# SDA381V3.net
KiCad netlist of a schematic drawn in EAGLE
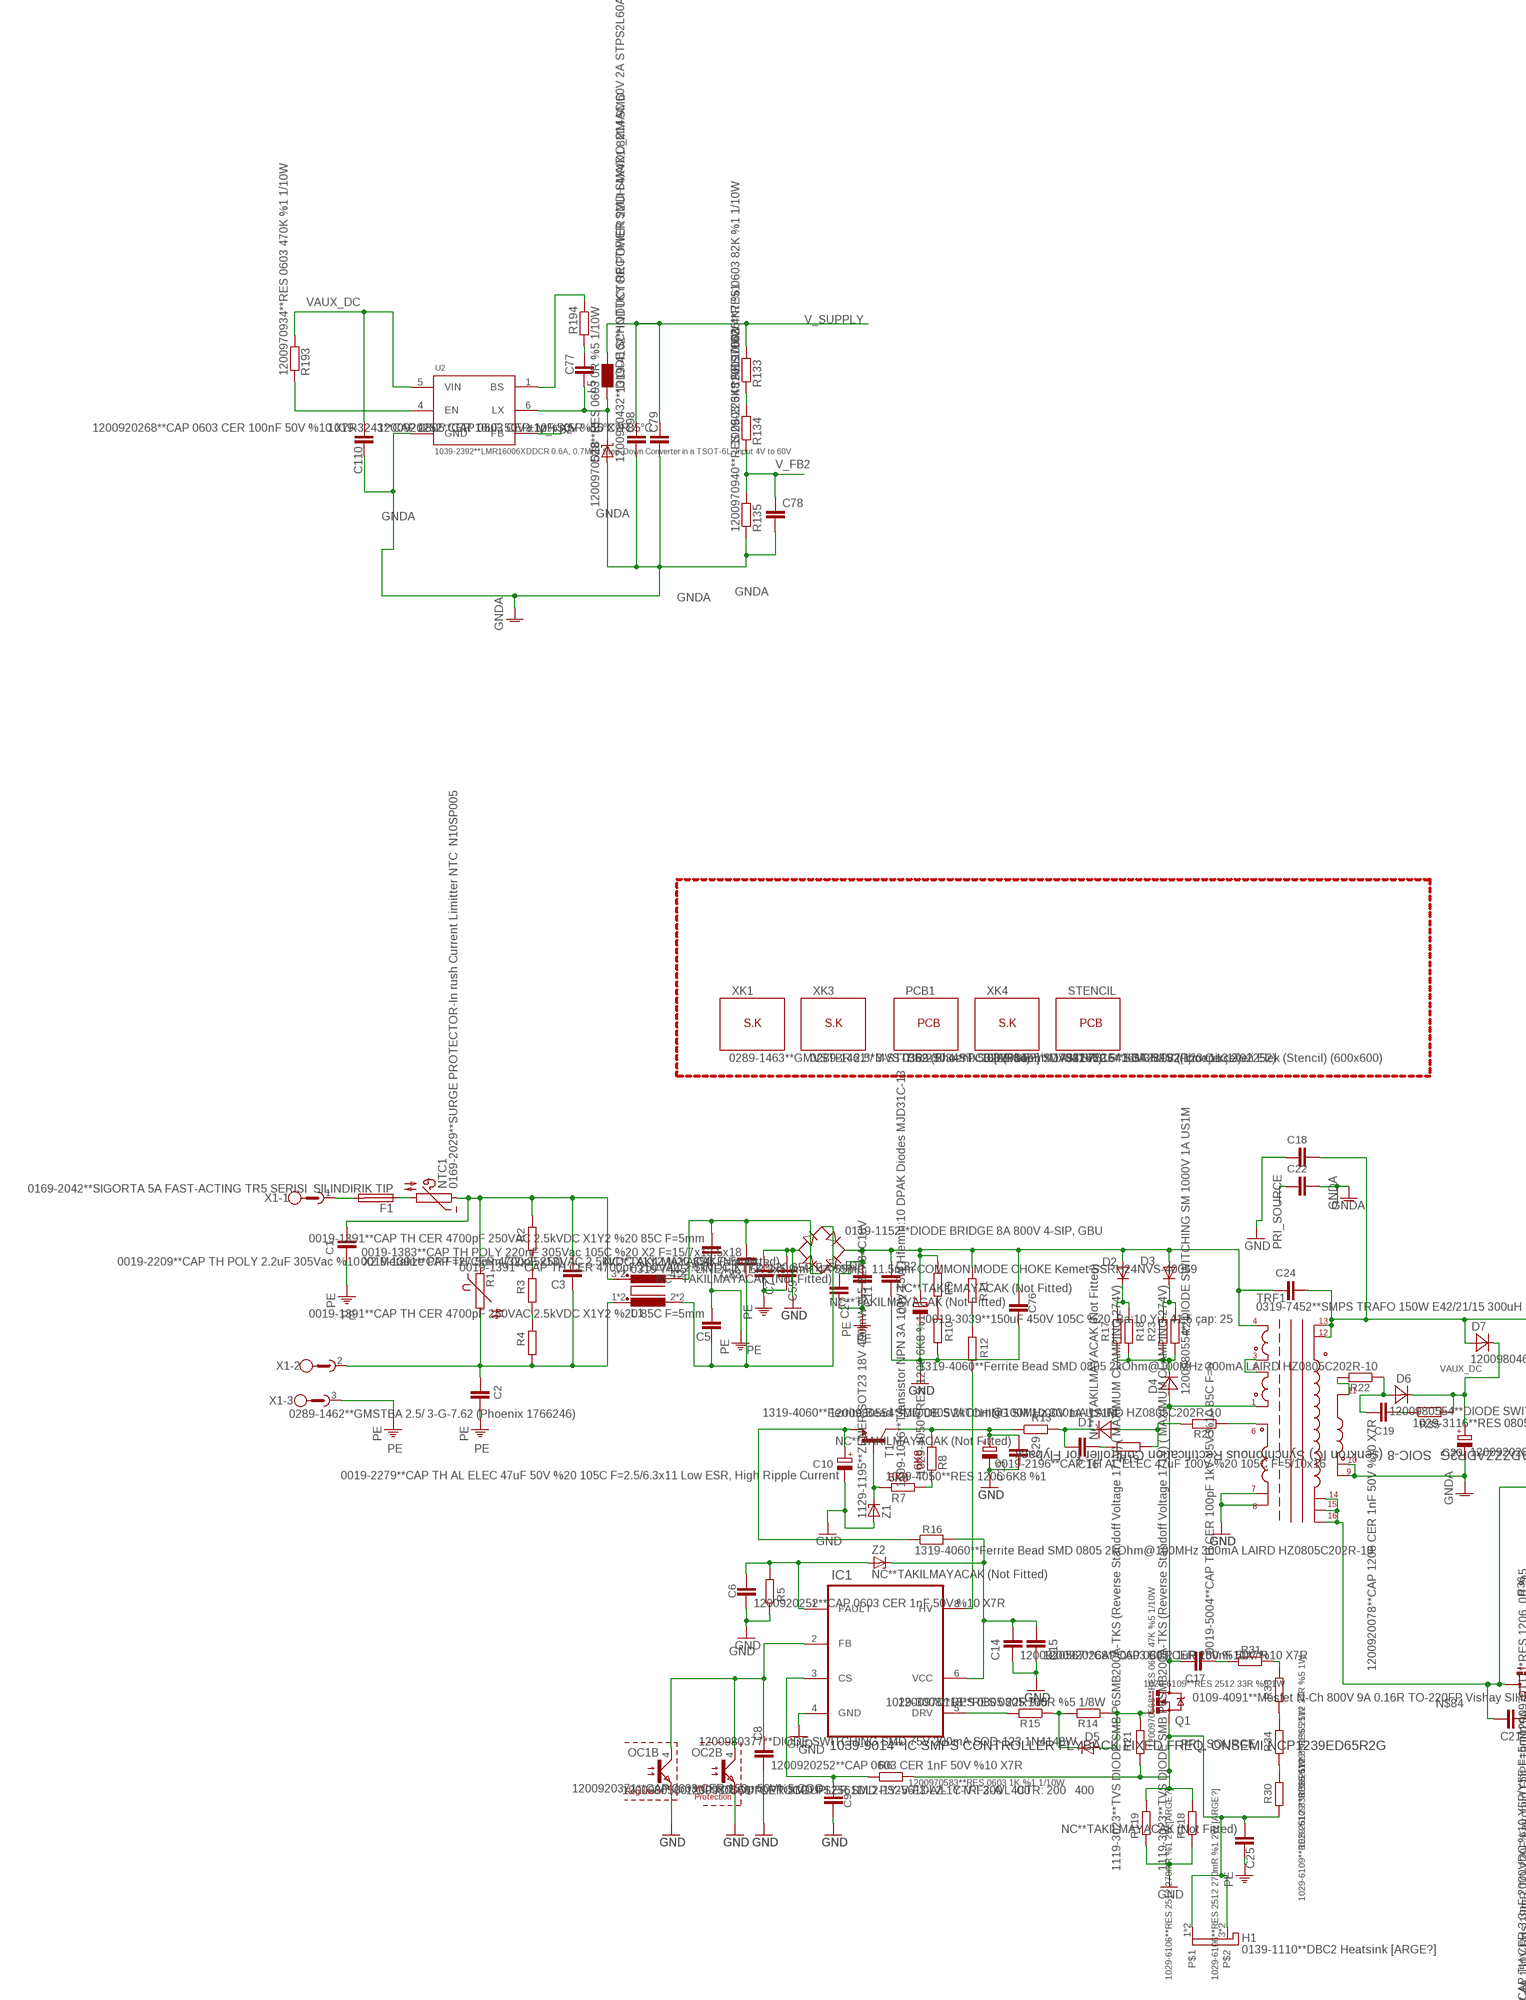
[diagram p0: schematic, sheet 1, part 1 of 3]
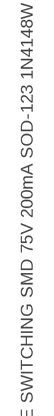
[diagram p1: schematic, sheet 1, part 2 of 3]
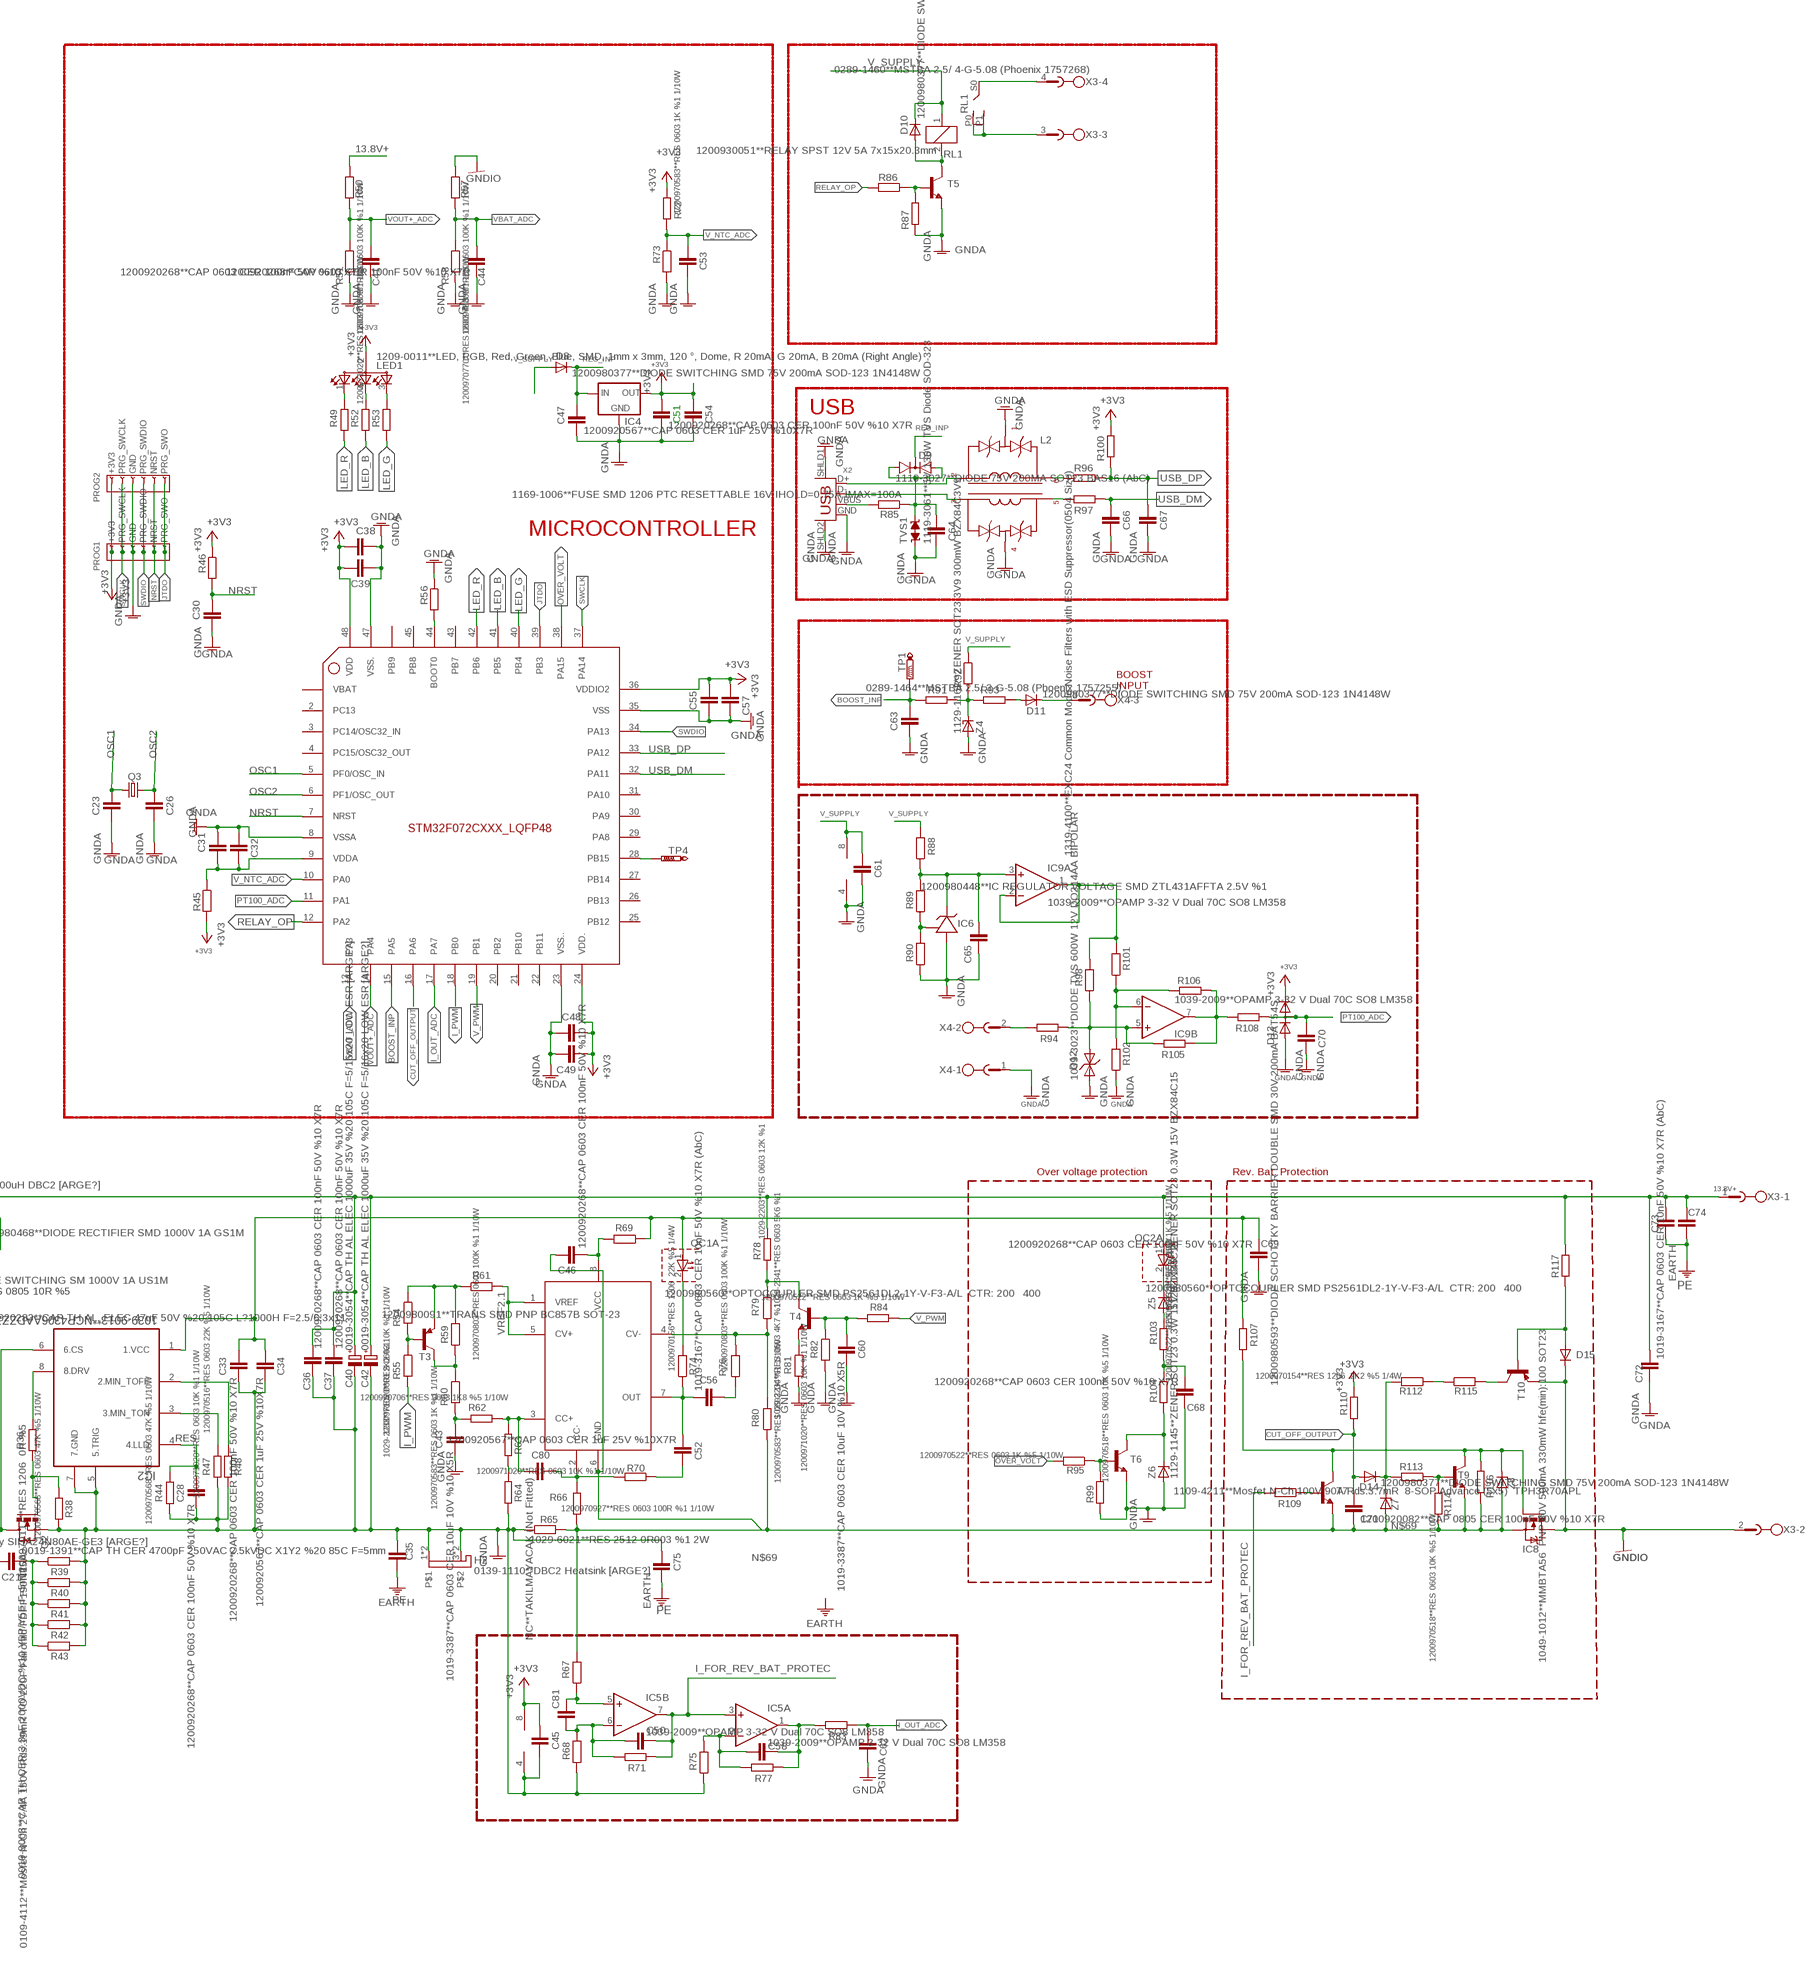
[diagram p2: schematic, sheet 1, part 3 of 3]

(export (version "E")
  (design (tool "Eeschema 10.0.6"))
  (components
    (comp (ref "B1")
      (value "0119-1152**DIODE BRIDGE 8A 800V 4-SIP, GBU")
      (footprint "eagle-import:DıODE_BRIDGE_8A_DIK")
      (libsource (lib "eagle-import") (part "DıODE_BRIDGE_8A_DIK"))
    )
    (comp (ref "C1")
      (value "NC**TAKILMAYACAK (Not Fitted)")
      (footprint "eagle-import:C50-035X75")
      (libsource (lib "eagle-import") (part "C50-035X75"))
    )
    (comp (ref "C2")
      (value "NC**TAKILMAYACAK (Not Fitted)")
      (footprint "eagle-import:C50-035X75")
      (libsource (lib "eagle-import") (part "C50-035X75"))
    )
    (comp (ref "C3")
      (value "0019-2209**CAP TH POLY 2.2uF 305Vac %10 X2 Metalize PP F=27.5mm (32x25x13)")
      (footprint "eagle-import:C275-113X316_&_C150-072X183_&_C225-113X268")
      (libsource (lib "eagle-import") (part "C275-113X316_&_C150-072X183_&_C225-113X268"))
    )
    (comp (ref "C4")
      (value "0019-1391**CAP TH CER 4700pF 250VAC 2.5kVDC X1Y2 %20 85C F=5mm")
      (footprint "eagle-import:C50-035X75")
      (libsource (lib "eagle-import") (part "C50-035X75"))
    )
    (comp (ref "C5")
      (value "0019-1391**CAP TH CER 4700pF 250VAC 2.5kVDC X1Y2 %20 85C F=5mm")
      (footprint "eagle-import:C50-035X75")
      (libsource (lib "eagle-import") (part "C50-035X75"))
    )
    (comp (ref "C6")
      (value "1200920252**CAP 0603 CER 1nF 50V %10 X7R")
      (footprint "eagle-import:C0603_ENKO")
      (libsource (lib "eagle-import") (part "C-EUC0603E"))
    )
    (comp (ref "C7")
      (value "0019-1391**CAP TH CER 4700pF 250VAC 2.5kVDC X1Y2 %20 85C F=5mm")
      (footprint "eagle-import:C50-035X75")
      (libsource (lib "eagle-import") (part "C50-035X75"))
    )
    (comp (ref "C8")
      (value "1200920252**CAP 0603 CER 1nF 50V %10 X7R")
      (footprint "eagle-import:C0603_ENKO")
      (libsource (lib "eagle-import") (part "C-EUC0603E"))
    )
    (comp (ref "C9")
      (value "1200920371**CAP 0603 CER 150p 50V%5 COG")
      (footprint "eagle-import:C0603_ENKO")
      (libsource (lib "eagle-import") (part "C-EUC0603E"))
    )
    (comp (ref "C10")
      (value "0019-2279**CAP TH AL ELEC 47uF 50V %20 105C F=2.5/6.3x11 Low ESR, High Ripple Current")
      (footprint "eagle-import:E2,5-7")
      (libsource (lib "eagle-import") (part "CPOL-EUE2.5-7"))
    )
    (comp (ref "C11")
      (value "0019-1391**CAP TH CER 4700pF 250VAC 2.5kVDC X1Y2 %20 85C F=5mm")
      (footprint "eagle-import:C50-035X75")
      (libsource (lib "eagle-import") (part "C50-035X75"))
    )
    (comp (ref "C12")
      (value "0019-3039**150uF 450V 105C %20 Ba:10 Yu: 41,5 çap: 25")
      (footprint "eagle-import:EB25D")
      (libsource (lib "eagle-import") (part "rcl_334_CPOL-EUE10-25"))
    )
    (comp (ref "C13")
      (value "0019-2196**CAP TH AL ELEC 47uF 100V %20 105C F=5/10x16")
      (footprint "eagle-import:E5-10,5")
      (libsource (lib "eagle-import") (part "CPOL-EUE5-10.5"))
    )
    (comp (ref "C14")
      (value "1200920567**CAP 0603 CER 1uF 25V %10X7R")
      (footprint "eagle-import:C0603_ENKO")
      (libsource (lib "eagle-import") (part "C-EUC0603E"))
    )
    (comp (ref "C15")
      (value "1200920268**CAP 0603 CER 100nF 50V %10 X7R")
      (footprint "eagle-import:C0603_ENKO")
      (libsource (lib "eagle-import") (part "C-EUC0603E"))
    )
    (comp (ref "C16")
      (value "NC**TAKILMAYACAK (Not Fitted)")
      (footprint "eagle-import:C1206_ENKO")
      (libsource (lib "eagle-import") (part "C-EUC1206E"))
    )
    (comp (ref "C17")
      (value "0019-5004**CAP TH CER 100pF 1kV Y5V %10 85C F=5")
      (footprint "eagle-import:C075-32X103_C050-035X75")
      (libsource (lib "eagle-import") (part "C075-32X103/C050-035X75"))
    )
    (comp (ref "C18")
      (value "1200920292**CAP TH CER 2.2nF 300Vac %20 X1Y2 F=7.5mm DxS(13x5)")
      (footprint "eagle-import:C075-32X103_DEIF")
      (libsource (lib "eagle-import") (part "C075-32X103_DEIF"))
    )
    (comp (ref "C19")
      (value "1200920078**CAP 1206 CER 1nF 50V %10 X7R")
      (footprint "eagle-import:C1206_ENKO")
      (libsource (lib "eagle-import") (part "C-EUC1206E"))
    )
    (comp (ref "C20")
      (value "1200920283**CAP TH AL. ELEC 47uF 50V %20 105C L?1000H F=2.5/6.3x11")
      (footprint "eagle-import:E2,5-7")
      (libsource (lib "eagle-import") (part "rcl_334_CPOL-EUE2.5-7"))
    )
    (comp (ref "C21")
      (value "0019-3003**CAP TH CER 3.3nF 2000VDC %10 Y5P/Y5E F=5mm")
      (footprint "eagle-import:C050-045X075")
      (libsource (lib "eagle-import") (part "C-EU050-045X075"))
    )
    (comp (ref "C22")
      (value "NC**TAKILMAYACAK (Not Fitted)")
      (footprint "eagle-import:C075-32X103_DEIF")
      (libsource (lib "eagle-import") (part "C075-32X103_DEIF"))
    )
    (comp (ref "C23")
      (value "1019-3352**CAP 0603 CER 22pF 50V %5 NPO")
      (footprint "eagle-import:C0603_ENKO")
      (libsource (lib "eagle-import") (part "C-EUC0603E"))
    )
    (comp (ref "C24")
      (value "NC**TAKILMAYACAK (Not Fitted)")
      (footprint "eagle-import:C075-32X103_DEIF")
      (libsource (lib "eagle-import") (part "C075-32X103_DEIF"))
    )
    (comp (ref "C25")
      (value "NC**TAKILMAYACAK (Not Fitted)")
      (footprint "eagle-import:C50-035X75")
      (libsource (lib "eagle-import") (part "C50-035X75"))
    )
    (comp (ref "C26")
      (value "1019-3352**CAP 0603 CER 22pF 50V %5 NPO")
      (footprint "eagle-import:C0603_ENKO")
      (libsource (lib "eagle-import") (part "C-EUC0603E"))
    )
    (comp (ref "C27")
      (value "NC**TAKILMAYACAK (Not Fitted)")
      (footprint "eagle-import:C50-035X75")
      (libsource (lib "eagle-import") (part "C50-035X75"))
    )
    (comp (ref "C28")
      (value "1200920268**CAP 0603 CER 100nF 50V %10 X7R")
      (footprint "eagle-import:C0603_ENKO")
      (libsource (lib "eagle-import") (part "C-EUC0603E"))
    )
    (comp (ref "C29")
      (value "NC**TAKILMAYACAK (Not Fitted)")
      (footprint "eagle-import:C1206_ENKO")
      (libsource (lib "eagle-import") (part "C-EUC1206E"))
    )
    (comp (ref "C30")
      (value "1200920268**CAP 0603 CER 100nF 50V %10 X7R")
      (footprint "eagle-import:C0603_ENKO")
      (libsource (lib "eagle-import") (part "C-EUC0603E"))
    )
    (comp (ref "C31")
      (value "1200920268**CAP 0603 CER 100nF 50V %10 X7R")
      (footprint "eagle-import:C0603_ENKO")
      (libsource (lib "eagle-import") (part "C-EUC0603E"))
    )
    (comp (ref "C32")
      (value "1019-3167**CAP 0603 CER 10nF 50V %10 X7R (AbC)")
      (footprint "eagle-import:C0603_ENKO")
      (libsource (lib "eagle-import") (part "C-EUC0603E"))
    )
    (comp (ref "C33")
      (value "1200920268**CAP 0603 CER 100nF 50V %10 X7R")
      (footprint "eagle-import:C0603_ENKO")
      (libsource (lib "eagle-import") (part "C-EUC0603E"))
    )
    (comp (ref "C34")
      (value "1200920567**CAP 0603 CER 1uF 25V %10X7R")
      (footprint "eagle-import:C0603_ENKO")
      (libsource (lib "eagle-import") (part "C-EUC0603E"))
    )
    (comp (ref "C35")
      (value "0019-1391**CAP TH CER 4700pF 250VAC 2.5kVDC X1Y2 %20 85C F=5mm")
      (footprint "eagle-import:C050-045X075")
      (libsource (lib "eagle-import") (part "C-EU050-045X075"))
    )
    (comp (ref "C36")
      (value "1200920268**CAP 0603 CER 100nF 50V %10 X7R")
      (footprint "eagle-import:C0603_ENKO")
      (libsource (lib "eagle-import") (part "C-EUC0603E"))
    )
    (comp (ref "C37")
      (value "1200920268**CAP 0603 CER 100nF 50V %10 X7R")
      (footprint "eagle-import:C0603_ENKO")
      (libsource (lib "eagle-import") (part "C-EUC0603E"))
    )
    (comp (ref "C38")
      (value "1200920268**CAP 0603 CER 100nF 50V %10 X7R")
      (footprint "eagle-import:C0603_ENKO")
      (libsource (lib "eagle-import") (part "C-EUC0603E"))
    )
    (comp (ref "C39")
      (value "1019-3167**CAP 0603 CER 10nF 50V %10 X7R (AbC)")
      (footprint "eagle-import:C0603_ENKO")
      (libsource (lib "eagle-import") (part "C-EUC0603E"))
    )
    (comp (ref "C40")
      (value "0019-3054**CAP TH AL ELEC 1000uF 35V %20 105C F=5/16x20 LOW ESR [ARGE?]")
      (footprint "eagle-import:E5-13_E7,5-16")
      (libsource (lib "eagle-import") (part "E5-13/E7,5-16"))
    )
    (comp (ref "C41")
      (value "1200920268**CAP 0603 CER 100nF 50V %10 X7R")
      (footprint "eagle-import:C0603_ENKO")
      (libsource (lib "eagle-import") (part "C-EUC0603E"))
    )
    (comp (ref "C42")
      (value "0019-3054**CAP TH AL ELEC 1000uF 35V %20 105C F=5/16x20 LOW ESR [ARGE?]")
      (footprint "eagle-import:E5-13_E7,5-16")
      (libsource (lib "eagle-import") (part "E5-13/E7,5-16"))
    )
    (comp (ref "C43")
      (value "1019-3387**CAP 0603 CER 10uF 10V %10 X5R")
      (footprint "eagle-import:C0603_ENKO")
      (libsource (lib "eagle-import") (part "C-EUC0603E"))
    )
    (comp (ref "C44")
      (value "1200920268**CAP 0603 CER 100nF 50V %10 X7R")
      (footprint "eagle-import:C0603_ENKO")
      (libsource (lib "eagle-import") (part "C-EUC0603E"))
    )
    (comp (ref "C45")
      (value "1200920268**CAP 0603 CER 100nF 50V %10 X7R")
      (footprint "eagle-import:C0603_ENKO")
      (libsource (lib "eagle-import") (part "C-EUC0603E"))
    )
    (comp (ref "C46")
      (value "1200920268**CAP 0603 CER 100nF 50V %10 X7R")
      (footprint "eagle-import:C0603_ENKO")
      (libsource (lib "eagle-import") (part "C-EUC0603E"))
    )
    (comp (ref "C47")
      (value "1200920567**CAP 0603 CER 1uF 25V %10X7R")
      (footprint "eagle-import:C0603_ENKO")
      (libsource (lib "eagle-import") (part "C-EUC0603E"))
    )
    (comp (ref "C48")
      (value "1019-3167**CAP 0603 CER 10nF 50V %10 X7R (AbC)")
      (footprint "eagle-import:C0603_ENKO")
      (libsource (lib "eagle-import") (part "C-EUC0603E"))
    )
    (comp (ref "C49")
      (value "1200920268**CAP 0603 CER 100nF 50V %10 X7R")
      (footprint "eagle-import:C0603_ENKO")
      (libsource (lib "eagle-import") (part "C-EUC0603E"))
    )
    (comp (ref "C50")
      (value "NC**TAKILMAYACAK (Not Fitted)")
      (footprint "eagle-import:C0603_ENKO")
      (libsource (lib "eagle-import") (part "C-EUC0603E"))
    )
    (comp (ref "C51")
      (value "1200920268**CAP 0603 CER 100nF 50V %10 X7R")
      (footprint "eagle-import:C0603_ENKO")
      (libsource (lib "eagle-import") (part "C-EUC0603E"))
    )
    (comp (ref "C52")
      (value "1200920567**CAP 0603 CER 1uF 25V %10X7R")
      (footprint "eagle-import:C0603_ENKO")
      (libsource (lib "eagle-import") (part "C-EUC0603E"))
    )
    (comp (ref "C53")
      (value "1200920268**CAP 0603 CER 100nF 50V %10 X7R")
      (footprint "eagle-import:C0603_ENKO")
      (libsource (lib "eagle-import") (part "C-EUC0603E"))
    )
    (comp (ref "C54")
      (value "1019-3301**CAP 0805 47uF 6.3V %20 X5R")
      (footprint "eagle-import:C0805_ENKO")
      (libsource (lib "eagle-import") (part "C-EUC0805E"))
    )
    (comp (ref "C55")
      (value "1019-3167**CAP 0603 CER 10nF 50V %10 X7R (AbC)")
      (footprint "eagle-import:C0603_ENKO")
      (libsource (lib "eagle-import") (part "C-EUC0603E"))
    )
    (comp (ref "C56")
      (value "1019-3167**CAP 0603 CER 10nF 50V %10 X7R (AbC)")
      (footprint "eagle-import:C0603_ENKO")
      (libsource (lib "eagle-import") (part "C-EUC0603E"))
    )
    (comp (ref "C57")
      (value "1200920268**CAP 0603 CER 100nF 50V %10 X7R")
      (footprint "eagle-import:C0603_ENKO")
      (libsource (lib "eagle-import") (part "C-EUC0603E"))
    )
    (comp (ref "C58")
      (value "1200920371**CAP 0603 CER 150p 50V%5 COG")
      (footprint "eagle-import:C0603_ENKO")
      (libsource (lib "eagle-import") (part "C-EUC0603E"))
    )
    (comp (ref "C59")
      (value "NC**TAKILMAYACAK (Not Fitted)")
      (footprint "eagle-import:C50-035X75")
      (libsource (lib "eagle-import") (part "C50-035X75"))
    )
    (comp (ref "C60")
      (value "1019-3387**CAP 0603 CER 10uF 10V %10 X5R")
      (footprint "eagle-import:C0603_ENKO")
      (libsource (lib "eagle-import") (part "C-EUC0603E"))
    )
    (comp (ref "C61")
      (value "1200920268**CAP 0603 CER 100nF 50V %10 X7R")
      (footprint "eagle-import:C0603_ENKO")
      (libsource (lib "eagle-import") (part "C-EUC0603E"))
    )
    (comp (ref "C62")
      (value "1200920268**CAP 0603 CER 100nF 50V %10 X7R")
      (footprint "eagle-import:C0603_ENKO")
      (libsource (lib "eagle-import") (part "C-EUC0603E"))
    )
    (comp (ref "C63")
      (value "1019-3167**CAP 0603 CER 10nF 50V %10 X7R (AbC)")
      (footprint "eagle-import:C0603_ENKO")
      (libsource (lib "eagle-import") (part "C-EUC0603E"))
    )
    (comp (ref "C64")
      (value "1200920268**CAP 0603 CER 100nF 50V %10 X7R")
      (footprint "eagle-import:C0603_ENKO")
      (libsource (lib "eagle-import") (part "C-EUC0603E"))
    )
    (comp (ref "C65")
      (value "1200920268**CAP 0603 CER 100nF 50V %10 X7R")
      (footprint "eagle-import:C0603_ENKO")
      (libsource (lib "eagle-import") (part "C-EUC0603E"))
    )
    (comp (ref "C66")
      (value "1019-3381**CAP 0603 CER 33pf 50V %5 NPO(COG)")
      (footprint "eagle-import:C0603_ENKO")
      (libsource (lib "eagle-import") (part "C-EUC0603E"))
    )
    (comp (ref "C67")
      (value "1019-3381**CAP 0603 CER 33pf 50V %5 NPO(COG)")
      (footprint "eagle-import:C0603_ENKO")
      (libsource (lib "eagle-import") (part "C-EUC0603E"))
    )
    (comp (ref "C68")
      (value "1200920268**CAP 0603 CER 100nF 50V %10 X7R")
      (footprint "eagle-import:C0603_ENKO")
      (libsource (lib "eagle-import") (part "C-EUC0603E"))
    )
    (comp (ref "C69")
      (value "1200920268**CAP 0603 CER 100nF 50V %10 X7R")
      (footprint "eagle-import:C0603_ENKO")
      (libsource (lib "eagle-import") (part "C-EUC0603E"))
    )
    (comp (ref "C70")
      (value "1200920268**CAP 0603 CER 100nF 50V %10 X7R")
      (footprint "eagle-import:C0603_ENKO")
      (libsource (lib "eagle-import") (part "C-EUC0603E"))
    )
    (comp (ref "C71")
      (value "1200920082**CAP 0805 CER 100nF 50V %10 X7R")
      (footprint "eagle-import:C0805_ENKO")
      (libsource (lib "eagle-import") (part "C-EUC0805E"))
    )
    (comp (ref "C72")
      (value "1019-3167**CAP 0603 CER 10nF 50V %10 X7R (AbC)")
      (footprint "eagle-import:C0603_ENKO")
      (libsource (lib "eagle-import") (part "C-EUC0603E"))
    )
    (comp (ref "C73")
      (value "0019-1391**CAP TH CER 4700pF 250VAC 2.5kVDC X1Y2 %20 85C F=5mm")
      (footprint "eagle-import:C050-035X075")
      (libsource (lib "eagle-import") (part "C-EU050-035X075"))
    )
    (comp (ref "C74")
      (value "NC**TAKILMAYACAK (Not Fitted)")
      (footprint "eagle-import:C050-035X075")
      (libsource (lib "eagle-import") (part "C-EU050-035X075"))
    )
    (comp (ref "C75")
      (value "NC**TAKILMAYACAK (Not Fitted)")
      (footprint "eagle-import:C050-035X075")
      (libsource (lib "eagle-import") (part "C-EU050-035X075"))
    )
    (comp (ref "C76")
      (value "NC**TAKILMAYACAK (Not Fitted)")
      (footprint "eagle-import:C065-052X106")
      (libsource (lib "eagle-import") (part "C065-052X106"))
    )
    (comp (ref "C77")
      (value "1200920268**CAP 0603 CER 100nF 50V %10 X7R")
      (footprint "eagle-import:C0603_ENKO")
      (libsource (lib "eagle-import") (part "C-EUC0603E"))
    )
    (comp (ref "C78")
      (value "1200920271**CAP 0603 CER 10pF 50V%10 COG")
      (footprint "eagle-import:C0603_ENKO")
      (libsource (lib "eagle-import") (part "C-EUC0603E"))
    )
    (comp (ref "C79")
      (value "1019-3243**CAP 0805 CER 10uF 50V ±10% X5R -55°C ~ 85°C")
      (footprint "eagle-import:C0805_ENKO")
      (libsource (lib "eagle-import") (part "C-EUC0805E"))
    )
    (comp (ref "C80")
      (value "NC**TAKILMAYACAK (Not Fitted)")
      (footprint "eagle-import:C0603_ENKO")
      (libsource (lib "eagle-import") (part "C-EUC0603E"))
    )
    (comp (ref "C81")
      (value "NC**TAKILMAYACAK (Not Fitted)")
      (footprint "eagle-import:C0603_ENKO")
      (libsource (lib "eagle-import") (part "C-EUC0603E"))
    )
    (comp (ref "C82")
      (value "NC**TAKILMAYACAK (Not Fitted)")
      (footprint "eagle-import:C150-091X182")
      (libsource (lib "eagle-import") (part "C-EU150-091X182"))
    )
    (comp (ref "C83")
      (value "0019-1383**CAP TH POLY 220nF 305Vac 105C %20 X2 F=15/7x13.5x18")
      (footprint "eagle-import:C150-091X182_C225-108X268")
      (libsource (lib "eagle-import") (part "C150-091X182_C225-108X268"))
    )
    (comp (ref "C98")
      (value "1200920252**CAP 0603 CER 1nF 50V %10 X7R")
      (footprint "eagle-import:C0603_ENKO")
      (libsource (lib "eagle-import") (part "C-EUC0603E"))
    )
    (comp (ref "C110")
      (value "1200920268**CAP 0603 CER 100nF 50V %10 X7R")
      (footprint "eagle-import:C0603_ENKO")
      (libsource (lib "eagle-import") (part "C-EUC0603E"))
    )
    (comp (ref "D1")
      (value "1200980554**DIODE SWITCHING SM 1000V 1A US1M")
      (footprint "eagle-import:M7_DC_DIYOT")
      (libsource (lib "eagle-import") (part "M7_DC_DIYOT"))
    )
    (comp (ref "D2")
      (value "1119-3023**TVS DIODE SMB P6SMB200A-TKS (Reverse Standoff Voltage 171V) ( MAXIMUM CLAMPING 274V)")
      (footprint "eagle-import:SMB")
      (libsource (lib "eagle-import") (part "DIODE-SMB"))
    )
    (comp (ref "D3")
      (value "1119-3023**TVS DIODE SMB P6SMB200A-TKS (Reverse Standoff Voltage 171V) ( MAXIMUM CLAMPING 274V)")
      (footprint "eagle-import:SMB")
      (libsource (lib "eagle-import") (part "DIODE-SMB"))
    )
    (comp (ref "D4")
      (value "1200980554**DIODE SWITCHING SM 1000V 1A US1M")
      (footprint "eagle-import:M7_DC_DIYOT")
      (libsource (lib "eagle-import") (part "M7_DC_DIYOT"))
    )
    (comp (ref "D5")
      (value "1200980377**DIODE SWITCHING SMD 75V 200mA SOD-123 1N4148W")
      (footprint "eagle-import:SOD123")
      (libsource (lib "eagle-import") (part "DIODE-SOD123"))
    )
    (comp (ref "D6")
      (value "1200980554**DIODE SWITCHING SM 1000V 1A US1M")
      (footprint "eagle-import:M7_DC_DIYOT")
      (libsource (lib "eagle-import") (part "M7_DC_DIYOT"))
    )
    (comp (ref "D7")
      (value "1200980468**DIODE RECTIFIER SMD 1000V 1A GS1M")
      (footprint "eagle-import:M7_DC_DIYOT")
      (libsource (lib "eagle-import") (part "M7_DC_DIYOT"))
    )
    (comp (ref "D8")
      (value "1200980377**DIODE SWITCHING SMD 75V 200mA SOD-123 1N4148W")
      (footprint "eagle-import:SOD123")
      (libsource (lib "eagle-import") (part "DIODE-SOD123"))
    )
    (comp (ref "D9")
      (value "1119-3027**DIODE 75V 200MA SOT23 BAS16 (AbC)")
      (footprint "eagle-import:SOT23")
      (libsource (lib "eagle-import") (part "DIODE-2AC|CASOT23"))
    )
    (comp (ref "D10")
      (value "1200980377**DIODE SWITCHING SMD 75V 200mA SOD-123 1N4148W")
      (footprint "eagle-import:SOD123")
      (libsource (lib "eagle-import") (part "DIODE-SOD123"))
    )
    (comp (ref "D11")
      (value "1200980377**DIODE SWITCHING SMD 75V 200mA SOD-123 1N4148W")
      (footprint "eagle-import:SOD123")
      (libsource (lib "eagle-import") (part "DIODE-SOD123"))
    )
    (comp (ref "D12")
      (value "1039-3023**DIODE TVS 600W 12V DO214AA BIPOLAR")
      (footprint "eagle-import:TRANSIL_SMB")
      (libsource (lib "eagle-import") (part "TRANSIL_SMB"))
    )
    (comp (ref "D13")
      (value "1200980593**DIODE SCHOTTKY BARRIER DOUBLE SMD 30V 200mA BAT54S")
      (footprint "eagle-import:SOT23")
      (libsource (lib "eagle-import") (part "BAV199"))
    )
    (comp (ref "D14")
      (value "1200980377**DIODE SWITCHING SMD 75V 200mA SOD-123 1N4148W")
      (footprint "eagle-import:SOD123")
      (libsource (lib "eagle-import") (part "DIODE-SOD123"))
    )
    (comp (ref "D15")
      (value "1200980377**DIODE SWITCHING SMD 75V 200mA SOD-123 1N4148W")
      (footprint "eagle-import:SOD123")
      (libsource (lib "eagle-import") (part "DIODE-SOD123"))
    )
    (comp (ref "D18")
      (value "1200980432**DIODE SCHOTTKY RECTIFIER SMD SMA/DO_214AC 60V 2A STPS2L60A")
      (footprint "eagle-import:SMA")
      (libsource (lib "eagle-import") (part "SD-SMA"))
    )
    (comp (ref "F1")
      (value "0169-2042**SIGORTA 5A FAST-ACTING TR5 SERISI SILINDIRIK TIP")
      (footprint "eagle-import:SENS_FUSE")
      (libsource (lib "eagle-import") (part "SENS_FUSE"))
    )
    (comp (ref "H1")
      (value "0139-1110**DBC2 Heatsink [ARGE?]")
      (footprint "eagle-import:DEIF_SOGUTUCU_2")
      (libsource (lib "eagle-import") (part "DEIF_SOGUTUCU_2"))
    )
    (comp (ref "H2")
      (value "0139-1110**DBC2 Heatsink [ARGE?]")
      (footprint "eagle-import:DEIF_SOGUTUCU_2")
      (libsource (lib "eagle-import") (part "DEIF_SOGUTUCU_2"))
    )
    (comp (ref "IC1")
      (value "1039-9014**IC SMPS CONTROLLER FLYBACK FIXED FREQ. ONSEMI NCP1239ED65R2G")
      (footprint "eagle-import:NCP1239_SMPS_IC")
      (libsource (lib "eagle-import") (part "NCP1239_SMPS_IC"))
    )
    (comp (ref "IC2")
      (value "1039-9013**NCP4306AADZZZADR2G SOIC-8 (senkron IC) Synchronous Rectification Controller for Flyback")
      (footprint "eagle-import:NCP4306")
      (libsource (lib "eagle-import") (part "NCP4306"))
    )
    (comp (ref "IC3")
      (value "1039-2224**TSM1011ID SO-8 Constant Voltage and Constant Current Controller")
      (footprint "eagle-import:SO-8")
      (libsource (lib "eagle-import") (part "TSM1011"))
    )
    (comp (ref "IC4")
      (value "1039-3003**Voltage Regulator SOT-89 3.3V Diodes AP2204RA-3.3TRG1")
      (footprint "eagle-import:SOT89")
      (libsource (lib "eagle-import") (part "S-812XSGUP"))
    )
    (comp (ref "IC5")
      (value "1039-2009**OPAMP 3-32 V Dual 70C SO8 LM358")
      (footprint "eagle-import:SO08")
      (libsource (lib "eagle-import") (part "LM358D"))
    )
    (comp (ref "IC6")
      (value "1200980448**IC REGULATOR VOLTAGE SMD ZTL431AFFTA 2.5V %1")
      (footprint "eagle-import:TL431_SOT23F")
      (libsource (lib "eagle-import") (part "TL431_SOT23F"))
    )
    (comp (ref "IC8")
      (value "1109-4211**Mosfet N-Ch 100V 90A Rds:3.7mR 8-SOP Advance (5x5) TPH3R70APL")
      (footprint "eagle-import:TPH6R30ANL")
      (libsource (lib "eagle-import") (part "TPH6R30ANL"))
    )
    (comp (ref "IC9")
      (value "1039-2009**OPAMP 3-32 V Dual 70C SO8 LM358")
      (footprint "eagle-import:SO08")
      (libsource (lib "eagle-import") (part "LM358D"))
    )
    (comp (ref "L1")
      (value "0319-7445**LINE FILTER 2x5,9mH 4A 55mR 11.5mm COMMON MODE CHOKE Kemet SSRH24NVS-40059")
      (footprint "eagle-import:UU1620_&_FWCMET24V")
      (libsource (lib "eagle-import") (part "UU1620_&_FWCMET24V"))
    )
    (comp (ref "L2")
      (value "1319-4100**EXC24 Common Mode Noise Filters with ESD Suppressor(0504 Size)")
      (footprint "eagle-import:EXC24CS_COMMON_MODE")
      (libsource (lib "eagle-import") (part "EXC24CS_COMMON_MODE"))
    )
    (comp (ref "L5")
      (value "1319-4102**INDUCTOR POWER 22UH 4X4X1.8MM SMD")
      (footprint "eagle-import:WE-PD2_5MM")
      (libsource (lib "eagle-import") (part "WE-PD2WE_PD2_5MM"))
    )
    (comp (ref "LED1")
      (value "1209-0011**LED, RGB, Red, Green, Blue, SMD, 1mm x 3mm, 120 °, Dome, R 20mA, G 20mA, B 20mA (Right Angle)")
      (footprint "eagle-import:KPFA-3010RGBC-11")
      (libsource (lib "eagle-import") (part "KPFA-3010RGBC-11"))
    )
    (comp (ref "NTC1")
      (value "0169-2029**SURGE PROTECTOR-In rush Current Limitter NTC N10SP005")
      (footprint "eagle-import:NTC_15R_2A_&_N15SP005-5")
      (libsource (lib "eagle-import") (part "NTC_15R_2A_&_N15SP005-5"))
    )
    (comp (ref "OC1")
      (value "1200980560**OPTOCOUPLER SMD PS2561DL2-1Y-V-F3-A/L  CTR: 200˜400")
      (footprint "eagle-import:PS2561DL2-1_OPTO1")
      (libsource (lib "eagle-import") (part "PS2561DL2-1_OPTO1"))
    )
    (comp (ref "OC2")
      (value "1200980560**OPTOCOUPLER SMD PS2561DL2-1Y-V-F3-A/L  CTR: 200˜400")
      (footprint "eagle-import:PS2561DL2-1_OPTO1")
      (libsource (lib "eagle-import") (part "PS2561DL2-1_OPTO1"))
    )
    (comp (ref "PCB1")
      (value "0369-5034**PCB [ARGE?] SDA381V2CF416M3HFS2(123x113.2)")
      (footprint "eagle-import:PCB")
      (libsource (lib "eagle-import") (part "PCB"))
    )
    (comp (ref "PROG1")
      (value "NC**TAKILMAYACAK (Not Fitted)")
      (footprint "eagle-import:PROG_6PIN")
      (libsource (lib "eagle-import") (part "PROG_6PIN"))
    )
    (comp (ref "PROG2")
      (value "NC**TAKILMAYACAK (Not Fitted)")
      (footprint "eagle-import:PROG_6PIN")
      (libsource (lib "eagle-import") (part "PROG_6PIN"))
    )
    (comp (ref "Q1")
      (value "0109-4091**Mosfet N-Ch 800V 9A 0.16R TO-220FP Vishay SIHA24N80AE-GE3 [ARGE?]")
      (footprint "eagle-import:TO220BV")
      (libsource (lib "eagle-import") (part "STP5NA50"))
    )
    (comp (ref "Q2")
      (value "0109-4112**Mosfet N-Ch 27.4A 150V Rds:19mR TO-220F Fairchild FDPF190N15A")
      (footprint "eagle-import:TO220BV")
      (libsource (lib "eagle-import") (part "STP5NA50"))
    )
    (comp (ref "Q3")
      (value "1149-0006**HC49S SMD KRISTAL 8MHZ -40+85 20PF 50PPM FAT Y3MM")
      (footprint "eagle-import:HC49UP")
      (libsource (lib "eagle-import") (part "CRYSTALHC49UP"))
    )
    (comp (ref "R1")
      (value "0169-2013**Varistor 20mm 300V")
      (footprint "eagle-import:S20K40")
      (libsource (lib "eagle-import") (part "S20K40"))
    )
    (comp (ref "R2")
      (value "1200970587**RES 1206 470K %5 1/4W")
      (footprint "eagle-import:R1206_ENKO")
      (libsource (lib "eagle-import") (part "R-EU_R1206E"))
    )
    (comp (ref "R3")
      (value "1200970587**RES 1206 470K %5 1/4W")
      (footprint "eagle-import:R1206_ENKO")
      (libsource (lib "eagle-import") (part "R-EU_R1206E"))
    )
    (comp (ref "R4")
      (value "1200970587**RES 1206 470K %5 1/4W")
      (footprint "eagle-import:R1206_ENKO")
      (libsource (lib "eagle-import") (part "R-EU_R1206E"))
    )
    (comp (ref "R5")
      (value "1200970687**RES 0603 56K %1 1/10W")
      (footprint "eagle-import:R0603_ENKO")
      (libsource (lib "eagle-import") (part "R-EU_R0603E"))
    )
    (comp (ref "R6")
      (value "1200970583**RES 0603 1K %1 1/10W")
      (footprint "eagle-import:R0603_ENKO")
      (libsource (lib "eagle-import") (part "R-EU_R0603E"))
    )
    (comp (ref "R7")
      (value "1029-4050**RES 1206 6K8 %1")
      (footprint "eagle-import:R1206_ENKO")
      (libsource (lib "eagle-import") (part "R-EU_R1206E"))
    )
    (comp (ref "R8")
      (value "1029-4050**RES 1206 6K8 %1")
      (footprint "eagle-import:R1206_ENKO")
      (libsource (lib "eagle-import") (part "R-EU_R1206E"))
    )
    (comp (ref "R9")
      (value "1200970179**RES 1206 330K %5 1/4W")
      (footprint "eagle-import:R1206_ENKO")
      (libsource (lib "eagle-import") (part "R-EU_R1206E"))
    )
    (comp (ref "R10")
      (value "1200970179**RES 1206 330K %5 1/4W")
      (footprint "eagle-import:R1206_ENKO")
      (libsource (lib "eagle-import") (part "R-EU_R1206E"))
    )
    (comp (ref "R11")
      (value "1200970154**RES 1206 2K2 %5 1/4W")
      (footprint "eagle-import:R1206_ENKO")
      (libsource (lib "eagle-import") (part "R-EU_R1206E"))
    )
    (comp (ref "R12")
      (value "1200970154**RES 1206 2K2 %5 1/4W")
      (footprint "eagle-import:R1206_ENKO")
      (libsource (lib "eagle-import") (part "R-EU_R1206E"))
    )
    (comp (ref "R13")
      (value "1200970601**RES 1206 10R %5 1/4W")
      (footprint "eagle-import:R1206_ENKO")
      (libsource (lib "eagle-import") (part "R-EU_R1206E"))
    )
    (comp (ref "R14")
      (value "1200970118**RES 0805 100R %5 1/8W")
      (footprint "eagle-import:R0805_ENKO")
      (libsource (lib "eagle-import") (part "R-EU_R0805E"))
    )
    (comp (ref "R15")
      (value "1029-3008**RES 0805 22R %5")
      (footprint "eagle-import:R0805_ENKO")
      (libsource (lib "eagle-import") (part "R-EU_R0805E"))
    )
    (comp (ref "R16")
      (value "1319-4060**Ferrite Bead SMD 0805 2kOhm@100MHz 300mA LAIRD HZ0805C202R-10")
      (footprint "eagle-import:R0805_ENKO")
      (libsource (lib "eagle-import") (part "R-EU_R0805E"))
    )
    (comp (ref "R17")
      (value "1029-3146**RES 1206 7R68 %1")
      (footprint "eagle-import:R1206_ENKO")
      (libsource (lib "eagle-import") (part "R-EU_R1206E"))
    )
    (comp (ref "R18")
      (value "1029-3146**RES 1206 7R68 %1")
      (footprint "eagle-import:R1206_ENKO")
      (libsource (lib "eagle-import") (part "R-EU_R1206E"))
    )
    (comp (ref "R19")
      (value "NC**TAKILMAYACAK (Not Fitted)")
      (footprint "eagle-import:R1206_ENKO")
      (libsource (lib "eagle-import") (part "R-EU_R1206E"))
    )
    (comp (ref "R20")
      (value "1319-4060**Ferrite Bead SMD 0805 2kOhm@100MHz 300mA LAIRD HZ0805C202R-10")
      (footprint "eagle-import:R0805_ENKO")
      (libsource (lib "eagle-import") (part "R-EU_R0805E"))
    )
    (comp (ref "R21")
      (value "1200970568**RES 0603 47K %5 1/10W")
      (footprint "eagle-import:R0603_ENKO")
      (libsource (lib "eagle-import") (part "R-EU_R0603E"))
    )
    (comp (ref "R22")
      (value "1319-4060**Ferrite Bead SMD 0805 2kOhm@100MHz 300mA LAIRD HZ0805C202R-10")
      (footprint "eagle-import:R0805_ENKO")
      (libsource (lib "eagle-import") (part "R-EU_R0805E"))
    )
    (comp (ref "R23")
      (value "1029-3146**RES 1206 7R68 %1")
      (footprint "eagle-import:R1206_ENKO")
      (libsource (lib "eagle-import") (part "R-EU_R1206E"))
    )
    (comp (ref "R24")
      (value "1029-3146**RES 1206 7R68 %1")
      (footprint "eagle-import:R1206_ENKO")
      (libsource (lib "eagle-import") (part "R-EU_R1206E"))
    )
    (comp (ref "R30")
      (value "1029-6109**RES 2512 33R %5 1W")
      (footprint "eagle-import:R2512")
      (libsource (lib "eagle-import") (part "R-EU_R2512"))
    )
    (comp (ref "R31")
      (value "1029-6109**RES 2512 33R %5 1W")
      (footprint "eagle-import:R2512")
      (libsource (lib "eagle-import") (part "R-EU_R2512"))
    )
    (comp (ref "R33")
      (value "1029-6109**RES 2512 33R %5 1W")
      (footprint "eagle-import:R2512")
      (libsource (lib "eagle-import") (part "R-EU_R2512"))
    )
    (comp (ref "R34")
      (value "1029-6109**RES 2512 33R %5 1W")
      (footprint "eagle-import:R2512")
      (libsource (lib "eagle-import") (part "R-EU_R2512"))
    )
    (comp (ref "R35")
      (value "1029-3116**RES 0805 10R %5")
      (footprint "eagle-import:R0805_ENKO")
      (libsource (lib "eagle-import") (part "R-EU_R0805E"))
    )
    (comp (ref "R36")
      (value "1200970117**RES 1206 0R %5")
      (footprint "eagle-import:R1206_ENKO")
      (libsource (lib "eagle-import") (part "R-EU_R1206E"))
    )
    (comp (ref "R38")
      (value "1200970568**RES 0603 47K %5 1/10W")
      (footprint "eagle-import:R0603_ENKO")
      (libsource (lib "eagle-import") (part "R-EU_R0603E"))
    )
    (comp (ref "R39")
      (value "1200970228**RES 1206 47R %5 1/4W")
      (footprint "eagle-import:R1206_ENKO")
      (libsource (lib "eagle-import") (part "R-EU_R1206E"))
    )
    (comp (ref "R40")
      (value "1200970228**RES 1206 47R %5 1/4W")
      (footprint "eagle-import:R1206_ENKO")
      (libsource (lib "eagle-import") (part "R-EU_R1206E"))
    )
    (comp (ref "R41")
      (value "1200970228**RES 1206 47R %5 1/4W")
      (footprint "eagle-import:R1206_ENKO")
      (libsource (lib "eagle-import") (part "R-EU_R1206E"))
    )
    (comp (ref "R42")
      (value "1200970228**RES 1206 47R %5 1/4W")
      (footprint "eagle-import:R1206_ENKO")
      (libsource (lib "eagle-import") (part "R-EU_R1206E"))
    )
    (comp (ref "R43")
      (value "1200970228**RES 1206 47R %5 1/4W")
      (footprint "eagle-import:R1206_ENKO")
      (libsource (lib "eagle-import") (part "R-EU_R1206E"))
    )
    (comp (ref "R44")
      (value "1200970568**RES 0603 47K %5 1/10W")
      (footprint "eagle-import:R0603_ENKO")
      (libsource (lib "eagle-import") (part "R-EU_R0603E"))
    )
    (comp (ref "R45")
      (value "1319-4060**Ferrite Bead SMD 0805 2kOhm@100MHz 300mA LAIRD HZ0805C202R-10")
      (footprint "eagle-import:R0805_ENKO")
      (libsource (lib "eagle-import") (part "R-EU_R0805E"))
    )
    (comp (ref "R46")
      (value "1200970518**RES 0603 10K %5 1/10W")
      (footprint "eagle-import:R0603_ENKO")
      (libsource (lib "eagle-import") (part "R-EU_R0603E"))
    )
    (comp (ref "R47")
      (value "1200971020**RES 0603 10K %1 1/10W")
      (footprint "eagle-import:R0603_ENKO")
      (libsource (lib "eagle-import") (part "R-EU_R0603E"))
    )
    (comp (ref "R48")
      (value "1200970516**RES 0603 22K %5 1/10W")
      (footprint "eagle-import:R0603_ENKO")
      (libsource (lib "eagle-import") (part "R-EU_R0603E"))
    )
    (comp (ref "R49")
      (value "1029-2005**RES 0603 220R %1")
      (footprint "eagle-import:R0603_ENKO")
      (libsource (lib "eagle-import") (part "R-EU_R0603E"))
    )
    (comp (ref "R50")
      (value "1200970803**RES 0603 100K %1 1/10W")
      (footprint "eagle-import:R0603_ENKO")
      (libsource (lib "eagle-import") (part "R-EU_R0603E"))
    )
    (comp (ref "R51")
      (value "1200971020**RES 0603 10K %1 1/10W")
      (footprint "eagle-import:R0603_ENKO")
      (libsource (lib "eagle-import") (part "R-EU_R0603E"))
    )
    (comp (ref "R52")
      (value "1029-2005**RES 0603 220R %1")
      (footprint "eagle-import:R0603_ENKO")
      (libsource (lib "eagle-import") (part "R-EU_R0603E"))
    )
    (comp (ref "R53")
      (value "1029-2005**RES 0603 220R %1")
      (footprint "eagle-import:R0603_ENKO")
      (libsource (lib "eagle-import") (part "R-EU_R0603E"))
    )
    (comp (ref "R54")
      (value "1200971020**RES 0603 10K %1 1/10W")
      (footprint "eagle-import:R0603_ENKO")
      (libsource (lib "eagle-import") (part "R-EU_R0603E"))
    )
    (comp (ref "R55")
      (value "1029-2233**RES 0603 2K2 %1")
      (footprint "eagle-import:R0603_ENKO")
      (libsource (lib "eagle-import") (part "rcl_334_R-EU_R0603E"))
    )
    (comp (ref "R56")
      (value "1200970522**RES 0603 1K %5 1/10W")
      (footprint "eagle-import:R0603_ENKO")
      (libsource (lib "eagle-import") (part "R-EU_R0603E"))
    )
    (comp (ref "R57")
      (value "1200970803**RES 0603 100K %1 1/10W")
      (footprint "eagle-import:R0603_ENKO")
      (libsource (lib "eagle-import") (part "R-EU_R0603E"))
    )
    (comp (ref "R58")
      (value "1200970770**RES 0603 4K3 %1 1/10W")
      (footprint "eagle-import:R0603_ENKO")
      (libsource (lib "eagle-import") (part "R-EU_R0603E"))
    )
    (comp (ref "R59")
      (value "1200970803**RES 0603 100K %1 1/10W")
      (footprint "eagle-import:R0603_ENKO")
      (libsource (lib "eagle-import") (part "R-EU_R0603E"))
    )
    (comp (ref "R60")
      (value "1200970583**RES 0603 1K %1 1/10W")
      (footprint "eagle-import:R0603_ENKO")
      (libsource (lib "eagle-import") (part "R-EU_R0603E"))
    )
    (comp (ref "R61")
      (value "1200970583**RES 0603 1K %1 1/10W")
      (footprint "eagle-import:R0603_ENKO")
      (libsource (lib "eagle-import") (part "R-EU_R0603E"))
    )
    (comp (ref "R62")
      (value "1200970706**RES 0603 1K8 %5 1/10W")
      (footprint "eagle-import:R0603_ENKO")
      (libsource (lib "eagle-import") (part "R-EU_R0603E"))
    )
    (comp (ref "R63")
      (value "1029-2003**RES 0603 10R %1")
      (footprint "eagle-import:R0603_ENKO")
      (libsource (lib "eagle-import") (part "R-EU_R0603E"))
    )
    (comp (ref "R64")
      (value "1029-2006**RES 0603 47R %1")
      (footprint "eagle-import:R0603_ENKO")
      (libsource (lib "eagle-import") (part "R-EU_R0603E"))
    )
    (comp (ref "R65")
      (value "1029-6021**RES 2512 0R003 %1 2W")
      (footprint "eagle-import:R2512")
      (libsource (lib "eagle-import") (part "R-EU_R2512"))
    )
    (comp (ref "R66")
      (value "1200970927**RES 0603 100R %1 1/10W")
      (footprint "eagle-import:R0603_ENKO")
      (libsource (lib "eagle-import") (part "R-EU_R0603E"))
    )
    (comp (ref "R67")
      (value "1200970522**RES 0603 1K %5 1/10W")
      (footprint "eagle-import:R0603_ENKO")
      (libsource (lib "eagle-import") (part "R-EU_R0603E"))
    )
    (comp (ref "R68")
      (value "1200970522**RES 0603 1K %5 1/10W")
      (footprint "eagle-import:R0603_ENKO")
      (libsource (lib "eagle-import") (part "R-EU_R0603E"))
    )
    (comp (ref "R69")
      (value "1029-3116**RES 0805 10R %5")
      (footprint "eagle-import:R0805_ENKO")
      (libsource (lib "eagle-import") (part "R-EU_R0805E"))
    )
    (comp (ref "R70")
      (value "1200971020**RES 0603 10K %1 1/10W")
      (footprint "eagle-import:R0603_ENKO")
      (libsource (lib "eagle-import") (part "rcl_334_R-EU_R0603E"))
    )
    (comp (ref "R71")
      (value "1029-2234**RES 0603 4K7 %1")
      (footprint "eagle-import:R0603_ENKO")
      (libsource (lib "eagle-import") (part "R-EU_R0603E"))
    )
    (comp (ref "R72")
      (value "1200970583**RES 0603 1K %1 1/10W")
      (footprint "eagle-import:R0603_ENKO")
      (libsource (lib "eagle-import") (part "R-EU_R0603E"))
    )
    (comp (ref "R73")
      (value "1169-1001**TSM2A103F3951RZ THINKING 0805 10K NTC 125C")
      (footprint "eagle-import:R0805_ENKO")
      (libsource (lib "eagle-import") (part "R-EU_R0805E"))
    )
    (comp (ref "R74")
      (value "1200970156**RES 1206 22K %5 1/4W")
      (footprint "eagle-import:R1206_ENKO")
      (libsource (lib "eagle-import") (part "R-EU_R1206E"))
    )
    (comp (ref "R75")
      (value "1200970583**RES 0603 1K %1 1/10W")
      (footprint "eagle-import:R0603_ENKO")
      (libsource (lib "eagle-import") (part "R-EU_R0603E"))
    )
    (comp (ref "R76")
      (value "1200970803**RES 0603 100K %1 1/10W")
      (footprint "eagle-import:R0603_ENKO")
      (libsource (lib "eagle-import") (part "rcl_334_R-EU_R0603E"))
    )
    (comp (ref "R77")
      (value "1029-6089**RES 0603 6K8 %5")
      (footprint "eagle-import:R0603_ENKO")
      (libsource (lib "eagle-import") (part "R-EU_R0603E"))
    )
    (comp (ref "R78")
      (value "1029-2203**RES 0603 12K %1")
      (footprint "eagle-import:R0603_ENKO")
      (libsource (lib "eagle-import") (part "R-EU_R0603E"))
    )
    (comp (ref "R79")
      (value "1029-2341**RES 0603 5K6 %1")
      (footprint "eagle-import:R0603_ENKO")
      (libsource (lib "eagle-import") (part "rcl_334_R-EU_R0603E"))
    )
    (comp (ref "R80")
      (value "1029-2234**RES 0603 4K7 %1")
      (footprint "eagle-import:R0603_ENKO")
      (libsource (lib "eagle-import") (part "rcl_334_R-EU_R0603E"))
    )
    (comp (ref "R81")
      (value "1200970583**RES 0603 1K %1 1/10W")
      (footprint "eagle-import:R0603_ENKO")
      (libsource (lib "eagle-import") (part "R-EU_R0603E"))
    )
    (comp (ref "R82")
      (value "1200971020**RES 0603 10K %1 1/10W")
      (footprint "eagle-import:R0603_ENKO")
      (libsource (lib "eagle-import") (part "R-EU_R0603E"))
    )
    (comp (ref "R83")
      (value "1200970522**RES 0603 1K %5 1/10W")
      (footprint "eagle-import:R0603_ENKO")
      (libsource (lib "eagle-import") (part "R-EU_R0603E"))
    )
    (comp (ref "R84")
      (value "1200970522**RES 0603 1K %5 1/10W")
      (footprint "eagle-import:R0603_ENKO")
      (libsource (lib "eagle-import") (part "R-EU_R0603E"))
    )
    (comp (ref "R85")
      (value "1169-1006**FUSE SMD 1206 PTC RESETTABLE 16V IHOLD=0.75A IMAX=100A")
      (footprint "eagle-import:R1206_ENKO")
      (libsource (lib "eagle-import") (part "R-EU_R1206E"))
    )
    (comp (ref "R86")
      (value "1200970522**RES 0603 1K %5 1/10W")
      (footprint "eagle-import:R0603_ENKO")
      (libsource (lib "eagle-import") (part "R-EU_R0603E"))
    )
    (comp (ref "R87")
      (value "1200970518**RES 0603 10K %5 1/10W")
      (footprint "eagle-import:R0603_ENKO")
      (libsource (lib "eagle-import") (part "R-EU_R0603E"))
    )
    (comp (ref "R88")
      (value "1029-2234**RES 0603 4K7 %1")
      (footprint "eagle-import:R0603_ENKO")
      (libsource (lib "eagle-import") (part "R-EU_R0603E"))
    )
    (comp (ref "R89")
      (value "1200970583**RES 0603 1K %1 1/10W")
      (footprint "eagle-import:R0603_ENKO")
      (libsource (lib "eagle-import") (part "R-EU_R0603E"))
    )
    (comp (ref "R90")
      (value "1029-2231**RES 0603 1K8 %1")
      (footprint "eagle-import:R0603_ENKO")
      (libsource (lib "eagle-import") (part "R-EU_R0603E"))
    )
    (comp (ref "R91")
      (value "1200970518**RES 0603 10K %5 1/10W")
      (footprint "eagle-import:R0603_ENKO")
      (libsource (lib "eagle-import") (part "R-EU_R0603E"))
    )
    (comp (ref "R92")
      (value "1200970568**RES 0603 47K %5 1/10W")
      (footprint "eagle-import:R0603_ENKO")
      (libsource (lib "eagle-import") (part "R-EU_R0603E"))
    )
    (comp (ref "R93")
      (value "1409-0025**RES 0603 470R %5 1/16W")
      (footprint "eagle-import:R0603_ENKO")
      (libsource (lib "eagle-import") (part "R-EU_R0603E"))
    )
    (comp (ref "R94")
      (value "1029-6086**RES 0603 22R %1")
      (footprint "eagle-import:R0603_ENKO")
      (libsource (lib "eagle-import") (part "R-EU_R0603E"))
    )
    (comp (ref "R95")
      (value "1200970522**RES 0603 1K %5 1/10W")
      (footprint "eagle-import:R0603_ENKO")
      (libsource (lib "eagle-import") (part "R-EU_R0603E"))
    )
    (comp (ref "R96")
      (value "1029-6086**RES 0603 22R %1")
      (footprint "eagle-import:R0603_ENKO")
      (libsource (lib "eagle-import") (part "R-EU_R0603E"))
    )
    (comp (ref "R97")
      (value "1029-6086**RES 0603 22R %1")
      (footprint "eagle-import:R0603_ENKO")
      (libsource (lib "eagle-import") (part "R-EU_R0603E"))
    )
    (comp (ref "R98")
      (value "1029-2234**RES 0603 4K7 %1")
      (footprint "eagle-import:R0603_ENKO")
      (libsource (lib "eagle-import") (part "R-EU_R0603E"))
    )
    (comp (ref "R99")
      (value "1200970518**RES 0603 10K %5 1/10W")
      (footprint "eagle-import:R0603_ENKO")
      (libsource (lib "eagle-import") (part "R-EU_R0603E"))
    )
    (comp (ref "R100")
      (value "1200970852**RES 0603 1K5 %5 1/10W ( <-1029-3501 )")
      (footprint "eagle-import:R0603_ENKO")
      (libsource (lib "eagle-import") (part "R-EU_R0603E"))
    )
    (comp (ref "R101")
      (value "1200970684**RES 0603 47K %1 1/10W")
      (footprint "eagle-import:R0603_ENKO")
      (libsource (lib "eagle-import") (part "R-EU_R0603E"))
    )
    (comp (ref "R102")
      (value "1200970583**RES 0603 1K %1 1/10W")
      (footprint "eagle-import:R0603_ENKO")
      (libsource (lib "eagle-import") (part "R-EU_R0603E"))
    )
    (comp (ref "R103")
      (value "1200970522**RES 0603 1K %5 1/10W")
      (footprint "eagle-import:R0603_ENKO")
      (libsource (lib "eagle-import") (part "R-EU_R0603E"))
    )
    (comp (ref "R104")
      (value "1200970522**RES 0603 1K %5 1/10W")
      (footprint "eagle-import:R0603_ENKO")
      (libsource (lib "eagle-import") (part "R-EU_R0603E"))
    )
    (comp (ref "R105")
      (value "1029-2229**RES 0603 120K %1")
      (footprint "eagle-import:R0603_ENKO")
      (libsource (lib "eagle-import") (part "R-EU_R0603E"))
    )
    (comp (ref "R106")
      (value "1029-2219**RES 0603 30K %1")
      (footprint "eagle-import:R0603_ENKO")
      (libsource (lib "eagle-import") (part "R-EU_R0603E"))
    )
    (comp (ref "R107")
      (value "1200970515**RES 0603 100K %5 1/10W")
      (footprint "eagle-import:R0603_ENKO")
      (libsource (lib "eagle-import") (part "R-EU_R0603E"))
    )
    (comp (ref "R108")
      (value "1200970730**RES 0603 560R %1 1/10W")
      (footprint "eagle-import:R0603_ENKO")
      (libsource (lib "eagle-import") (part "R-EU_R0603E"))
    )
    (comp (ref "R109")
      (value "1200970518**RES 0603 10K %5 1/10W")
      (footprint "eagle-import:R0603_ENKO")
      (libsource (lib "eagle-import") (part "R-EU_R0603E"))
    )
    (comp (ref "R110")
      (value "1200970516**RES 0603 22K %5 1/10W")
      (footprint "eagle-import:R0603_ENKO")
      (libsource (lib "eagle-import") (part "R-EU_R0603E"))
    )
    (comp (ref "R112")
      (value "1200970154**RES 1206 2K2 %5 1/4W")
      (footprint "eagle-import:R1206_ENKO")
      (libsource (lib "eagle-import") (part "R-EU_R1206E"))
    )
    (comp (ref "R113")
      (value "1200970121**RES 0805 1K %5 1/8W")
      (footprint "eagle-import:R0805_ENKO")
      (libsource (lib "eagle-import") (part "R-EU_R0805E"))
    )
    (comp (ref "R114")
      (value "1200970518**RES 0603 10K %5 1/10W")
      (footprint "eagle-import:R0603_ENKO")
      (libsource (lib "eagle-import") (part "R-EU_R0603E"))
    )
    (comp (ref "R115")
      (value "1200970853**RES 1206 39K %1 1/4W")
      (footprint "eagle-import:R1206_ENKO")
      (libsource (lib "eagle-import") (part "R-EU_R1206E"))
    )
    (comp (ref "R116")
      (value "1200970585**RES 0603 1M %5 1/10W")
      (footprint "eagle-import:R0603_ENKO")
      (libsource (lib "eagle-import") (part "R-EU_R0603E"))
    )
    (comp (ref "R117")
      (value "1029-6015**RES 1206 56K %5")
      (footprint "eagle-import:R1206_ENKO")
      (libsource (lib "eagle-import") (part "R-EU_R1206E"))
    )
    (comp (ref "R118")
      (value "1029-6106**RES 2512 270mR %1 2W [ARGE?]")
      (footprint "eagle-import:R2512")
      (libsource (lib "eagle-import") (part "R-EU_R2512"))
    )
    (comp (ref "R119")
      (value "1029-6106**RES 2512 270mR %1 2W [ARGE?]")
      (footprint "eagle-import:R2512")
      (libsource (lib "eagle-import") (part "R-EU_R2512"))
    )
    (comp (ref "R133")
      (value "1200970626**RES 0603 82K %1 1/10W")
      (footprint "eagle-import:R0603_ENKO")
      (libsource (lib "eagle-import") (part "R-EU_R0603E"))
    )
    (comp (ref "R134")
      (value "1029-2234**RES 0603 4K7 %1")
      (footprint "eagle-import:R0603_ENKO")
      (libsource (lib "eagle-import") (part "R-EU_R0603E"))
    )
    (comp (ref "R135")
      (value "1200970940**RES 0603 6K8 %1 1/10W")
      (footprint "eagle-import:R0603_ENKO")
      (libsource (lib "eagle-import") (part "R-EU_R0603E"))
    )
    (comp (ref "R193")
      (value "1200970934**RES 0603 470K %1 1/10W")
      (footprint "eagle-import:R0603_ENKO")
      (libsource (lib "eagle-import") (part "R-EU_R0603E"))
    )
    (comp (ref "R194")
      (value "1200970528**RES 0603 0R %5 1/10W")
      (footprint "eagle-import:R0603_ENKO")
      (libsource (lib "eagle-import") (part "R-EU_R0603E"))
    )
    (comp (ref "RL1")
      (value "1200930051**RELAY SPST 12V 5A 7x15x20.3mm")
      (footprint "eagle-import:ALD1_AND_ALJ_RELAY")
      (libsource (lib "eagle-import") (part "ALD1_AND_ALJ_RELAY"))
    )
    (comp (ref "STENCIL")
      (value "041-7516**SDA381V2 için Çerçeveli Elek (Stencil) (600x600)")
      (footprint "eagle-import:PCB")
      (libsource (lib "eagle-import") (part "PCB"))
    )
    (comp (ref "T1")
      (value "1109-1016**Transistor NPN 3A 100V 15W Hfemin:10 DPAK Diodes MJD31C-13")
      (footprint "eagle-import:DPAK")
      (libsource (lib "eagle-import") (part "MJD31C"))
    )
    (comp (ref "T3")
      (value "1200980091**TRANS SMD PNP BC857B SOT-23")
      (footprint "eagle-import:SOT23-BEC")
      (libsource (lib "eagle-import") (part "-PNP-SOT23-BECBC856B"))
    )
    (comp (ref "T4")
      (value "1200980090**TRANS SMD NPN BC847B SOT-23")
      (footprint "eagle-import:SOT23")
      (libsource (lib "eagle-import") (part "BC848SMDALT1"))
    )
    (comp (ref "T5")
      (value "1200980090**TRANS SMD NPN BC847B SOT-23")
      (footprint "eagle-import:SOT23")
      (libsource (lib "eagle-import") (part "BC848SMDALT1"))
    )
    (comp (ref "T6")
      (value "1200980090**TRANS SMD NPN BC847B SOT-23")
      (footprint "eagle-import:SOT23")
      (libsource (lib "eagle-import") (part "BC848SMDALT1"))
    )
    (comp (ref "T7")
      (value "1200980090**TRANS SMD NPN BC847B SOT-23")
      (footprint "eagle-import:SOT23")
      (libsource (lib "eagle-import") (part "BC848SMDALT1"))
    )
    (comp (ref "T9")
      (value "1200980090**TRANS SMD NPN BC847B SOT-23")
      (footprint "eagle-import:SOT23")
      (libsource (lib "eagle-import") (part "BC848SMDALT1"))
    )
    (comp (ref "T10")
      (value "1049-1012**MMBTA56 PNP 80V 500mA 330mW hfe(min):100 SOT23")
      (footprint "eagle-import:SOT23-BEC")
      (libsource (lib "eagle-import") (part "-PNP-SOT23-BECBC856B"))
    )
    (comp (ref "TP1")
      (value "PTR1TP20R")
      (footprint "eagle-import:TP20R")
      (libsource (lib "eagle-import") (part "PTR1TP20R"))
    )
    (comp (ref "TP4")
      (value "PTR1TP20R")
      (footprint "eagle-import:TP20R")
      (libsource (lib "eagle-import") (part "PTR1TP20R"))
    )
    (comp (ref "TRF1")
      (value "0319-7452**SMPS TRAFO 150W E42/21/15 300uH DBC2 [ARGE?]")
      (footprint "eagle-import:DEIF_TRF")
      (libsource (lib "eagle-import") (part "DEIF_TRF"))
    )
    (comp (ref "TVS1")
      (value "1119-3061**5V 130W TVS Diode SOD-323")
      (footprint "eagle-import:SOD323")
      (libsource (lib "eagle-import") (part "TVS-BD-SOD323"))
    )
    (comp (ref "U1")
      (value "1039-2220**STM32F072C8T6 64K Flash USB, CAN")
      (footprint "eagle-import:STM32F072CXXX_LQFP48")
      (libsource (lib "eagle-import") (part "STM32F072CXXX_LQFP48"))
    )
    (comp (ref "U2")
      (value "1039-2392**LMR16006XDDCR 0.6A, 0.7MHz Step-Down Converter in a TSOT-6L, Input 4V to 60V")
      (footprint "eagle-import:AOZ1282CI-1")
      (libsource (lib "eagle-import") (part "AOZ1282CI-1"))
    )
    (comp (ref "X1")
      (value "0289-1462**GMSTBA 2.5/ 3-G-7.62 (Phoenix 1766246)")
      (footprint "eagle-import:GMSTBA3")
      (fields (field (name "MF") "FARNELL") (field (name "MPN") "1757255"))
      (libsource (lib "eagle-import") (part "GMSTBA3"))
    )
    (comp (ref "X2")
      (value "0309-1064**USB Type-B Mini Connector Horizantal")
      (footprint "eagle-import:USB_B(YATIK)")
      (libsource (lib "eagle-import") (part "USB_B(YATIK)"))
    )
    (comp (ref "X3")
      (value "0289-1460**MSTBA 2.5/ 4-G-5.08 (Phoenix 1757268)")
      (footprint "eagle-import:MSTBA4")
      (fields (field (name "MF") "FARNELL") (field (name "MPN") "1757268"))
      (libsource (lib "eagle-import") (part "MSTBA4"))
    )
    (comp (ref "X4")
      (value "0289-1464**MSTBA 2.5/ 3-G-5.08 (Phoenix 1757255)")
      (footprint "eagle-import:MSTBA3")
      (fields (field (name "MF") "FARNELL") (field (name "MPN") "1757255"))
      (libsource (lib "eagle-import") (part "MSTBA3"))
    )
    (comp (ref "XK1")
      (value "0289-1463**GMVSTBR 2.5/ 3-ST-7.62 (Phoenix 1832536)")
      (footprint "eagle-import:SOKET")
      (libsource (lib "eagle-import") (part "SOKET"))
    )
    (comp (ref "XK3")
      (value "0289-1461**MVSTBR 2.5/ 4-ST-5.08 (Phoenix 1792265)")
      (footprint "eagle-import:SOKET")
      (libsource (lib "eagle-import") (part "SOKET"))
    )
    (comp (ref "XK4")
      (value "0289-1465**MVSTBR 2.5/ 3-ST-5.08 (Phoenix 1792252)")
      (footprint "eagle-import:SOKET")
      (libsource (lib "eagle-import") (part "SOKET"))
    )
    (comp (ref "Z1")
      (value "1129-1195**ZENER SOT23 18V 400mW %5 BZX84C18V")
      (footprint "eagle-import:SOT23")
      (libsource (lib "eagle-import") (part "ZENER-DIODESOT23"))
    )
    (comp (ref "Z2")
      (value "NC**TAKILMAYACAK (Not Fitted)")
      (footprint "eagle-import:SOT23")
      (libsource (lib "eagle-import") (part "ZENER-DIODESOT23"))
    )
    (comp (ref "Z4")
      (value "1129-1162**ZENER SOT23 3V9 300mW BZX84C3V9")
      (footprint "eagle-import:SOT23")
      (libsource (lib "eagle-import") (part "ZENER-DIODESOT23"))
    )
    (comp (ref "Z5")
      (value "1129-1145**ZENER SOT23 0.3W 15V BZX84C15")
      (footprint "eagle-import:SOT23")
      (libsource (lib "eagle-import") (part "ZENER-DIODESOT23"))
    )
    (comp (ref "Z6")
      (value "1129-1145**ZENER SOT23 0.3W 15V BZX84C15")
      (footprint "eagle-import:SOT23")
      (libsource (lib "eagle-import") (part "ZENER-DIODESOT23"))
    )
    (comp (ref "Z7")
      (value "1129-1151**ZENER SOT23 12V 225mW BZX84C12")
      (footprint "eagle-import:SOT23")
      (libsource (lib "eagle-import") (part "ZENER-DIODESOT23"))
    )
    (comp (ref "Z8")
      (value "1129-1140**ZENER SOT23 5V1 0.4W BZX84C5V1")
      (footprint "eagle-import:SOT23")
      (libsource (lib "eagle-import") (part "ZENER-DIODESOT23"))
    )
  )
  (nets
    (net (code "1") (name "+3V3") (class "Default")
      (node (ref "C38") (pin "1") (pinfunction "1_1") (pintype "passive"))
      (node (ref "C39") (pin "1") (pinfunction "1_1") (pintype "passive"))
      (node (ref "C45") (pin "1") (pinfunction "1_1") (pintype "passive"))
      (node (ref "C48") (pin "1") (pinfunction "1_1") (pintype "passive"))
      (node (ref "C49") (pin "1") (pinfunction "1_1") (pintype "passive"))
      (node (ref "C51") (pin "1") (pinfunction "1_1") (pintype "passive"))
      (node (ref "C54") (pin "1") (pinfunction "1_1") (pintype "passive"))
      (node (ref "C55") (pin "1") (pinfunction "1_1") (pintype "passive"))
      (node (ref "C57") (pin "1") (pinfunction "1_1") (pintype "passive"))
      (node (ref "D13") (pin "2") (pinfunction "C_2") (pintype "passive"))
      (node (ref "IC4") (pin "3") (pinfunction "OUT_3") (pintype "passive"))
      (node (ref "IC5") (pin "8") (pinfunction "V+_8") (pintype "power_in"))
      (node (ref "LED1") (pin "2") (pinfunction "2_2") (pintype "passive"))
      (node (ref "PROG1") (pin "1") (pinfunction "+3V3_1") (pintype "passive"))
      (node (ref "PROG2") (pin "1") (pinfunction "+3V3_1") (pintype "passive"))
      (node (ref "R100") (pin "2") (pinfunction "2_2") (pintype "passive"))
      (node (ref "R110") (pin "2") (pinfunction "2_2") (pintype "passive"))
      (node (ref "R45") (pin "2") (pinfunction "2_2") (pintype "passive"))
      (node (ref "R46") (pin "1") (pinfunction "1_1") (pintype "passive"))
      (node (ref "R72") (pin "2") (pinfunction "2_2") (pintype "passive"))
      (node (ref "U1") (pin "24") (pinfunction "VDD._24") (pintype "bidirectional"))
      (node (ref "U1") (pin "36") (pinfunction "VDDIO2_36") (pintype "bidirectional"))
      (node (ref "U1") (pin "48") (pinfunction "VDD_48") (pintype "bidirectional"))
    )
    (net (code "2") (name "/13.8V+") (class "Default")
      (node (ref "C18") (pin "P$1") (pinfunction "1_P$1") (pintype "passive"))
      (node (ref "C24") (pin "P$1") (pinfunction "1_P$1") (pintype "passive"))
      (node (ref "C36") (pin "1") (pinfunction "1_1") (pintype "passive"))
      (node (ref "C37") (pin "1") (pinfunction "1_1") (pintype "passive"))
      (node (ref "C40") (pin "+") (pinfunction "+_+") (pintype "passive"))
      (node (ref "C40") (pin "+1") (pinfunction "+_+1") (pintype "passive"))
      (node (ref "C42") (pin "+") (pinfunction "+_+") (pintype "passive"))
      (node (ref "C42") (pin "+1") (pinfunction "+_+1") (pintype "passive"))
      (node (ref "C72") (pin "2") (pinfunction "2_2") (pintype "passive"))
      (node (ref "C73") (pin "1") (pinfunction "1_1") (pintype "passive"))
      (node (ref "C74") (pin "1") (pinfunction "1_1") (pintype "passive"))
      (node (ref "D7") (pin "A") (pinfunction "A_A") (pintype "passive"))
      (node (ref "OC2") (pin "1") (pinfunction "1_1") (pintype "passive"))
      (node (ref "R117") (pin "1") (pinfunction "1_1") (pintype "passive"))
      (node (ref "R50") (pin "1") (pinfunction "1_1") (pintype "passive"))
      (node (ref "R78") (pin "2") (pinfunction "2_2") (pintype "passive"))
      (node (ref "TRF1") (pin "10") (pinfunction "13_10") (pintype "passive"))
      (node (ref "TRF1") (pin "21") (pinfunction "13_21") (pintype "passive"))
      (node (ref "TRF1") (pin "22") (pinfunction "12_22") (pintype "passive"))
      (node (ref "TRF1") (pin "29") (pinfunction "12_29") (pintype "passive"))
      (node (ref "TRF1") (pin "30") (pinfunction "13_30") (pintype "passive"))
      (node (ref "TRF1") (pin "43") (pinfunction "12_43") (pintype "passive"))
      (node (ref "TRF1") (pin "44") (pinfunction "13_44") (pintype "passive"))
      (node (ref "TRF1") (pin "9") (pinfunction "12_9") (pintype "passive"))
      (node (ref "X3") (pin "1") (pinfunction "1_1") (pintype "passive"))
    )
    (net (code "3") (name "/I_FOR_REV_BAT_PROTEC") (class "Default")
      (node (ref "C50") (pin "2") (pinfunction "2_2") (pintype "passive"))
      (node (ref "IC5") (pin "3") (pinfunction "+IN_3") (pintype "input"))
      (node (ref "IC5") (pin "7") (pinfunction "OUT_7") (pintype "output"))
      (node (ref "R109") (pin "2") (pinfunction "2_2") (pintype "passive"))
      (node (ref "R71") (pin "2") (pinfunction "2_2") (pintype "passive"))
    )
    (net (code "4") (name "/N$69") (class "Default")
      (node (ref "C46") (pin "1") (pinfunction "1_1") (pintype "passive"))
      (node (ref "C71") (pin "2") (pinfunction "2_2") (pintype "passive"))
      (node (ref "IC3") (pin "6") (pinfunction "GND_6") (pintype "power_in"))
      (node (ref "IC8") (pin "S") (pinfunction "S123_S") (pintype "passive"))
      (node (ref "IC8") (pin "S1") (pinfunction "S123_S1") (pintype "passive"))
      (node (ref "IC8") (pin "S2") (pinfunction "S123_S2") (pintype "passive"))
      (node (ref "R114") (pin "2") (pinfunction "2_2") (pintype "passive"))
      (node (ref "R116") (pin "1") (pinfunction "1_1") (pintype "passive"))
      (node (ref "R65") (pin "2") (pinfunction "2_2") (pintype "passive"))
      (node (ref "R66") (pin "2") (pinfunction "2_2") (pintype "passive"))
      (node (ref "R67") (pin "2") (pinfunction "2_2") (pintype "passive"))
      (node (ref "R80") (pin "1") (pinfunction "1_1") (pintype "passive"))
      (node (ref "T7") (pin "2") (pinfunction "E_2") (pintype "passive"))
      (node (ref "T9") (pin "2") (pinfunction "E_2") (pintype "passive"))
      (node (ref "Z7") (pin "1") (pinfunction "A_1") (pintype "passive"))
      (node (ref "Z8") (pin "1") (pinfunction "A_1") (pintype "passive"))
    )
    (net (code "5") (name "/N$84") (class "Default")
      (node (ref "C21") (pin "1") (pinfunction "1_1") (pintype "passive"))
      (node (ref "IC2") (pin "6") (pinfunction "6.CS_6") (pintype "input"))
      (node (ref "Q2") (pin "D") (pinfunction "D_D") (pintype "passive"))
      (node (ref "TRF1") (pin "11") (pinfunction "14_11") (pintype "passive"))
      (node (ref "TRF1") (pin "12") (pinfunction "15_12") (pintype "passive"))
      (node (ref "TRF1") (pin "13") (pinfunction "16_13") (pintype "passive"))
      (node (ref "TRF1") (pin "19") (pinfunction "15_19") (pintype "passive"))
      (node (ref "TRF1") (pin "20") (pinfunction "14_20") (pintype "passive"))
      (node (ref "TRF1") (pin "25") (pinfunction "16_25") (pintype "passive"))
      (node (ref "TRF1") (pin "31") (pinfunction "14_31") (pintype "passive"))
      (node (ref "TRF1") (pin "32") (pinfunction "15_32") (pintype "passive"))
      (node (ref "TRF1") (pin "38") (pinfunction "16_38") (pintype "passive"))
      (node (ref "TRF1") (pin "45") (pinfunction "14_45") (pintype "passive"))
      (node (ref "TRF1") (pin "46") (pinfunction "15_46") (pintype "passive"))
      (node (ref "TRF1") (pin "47") (pinfunction "16_47") (pintype "passive"))
    )
    (net (code "6") (name "/OSC1") (class "Default")
      (node (ref "C23") (pin "1") (pinfunction "1_1") (pintype "passive"))
      (node (ref "Q3") (pin "1") (pinfunction "1_1") (pintype "passive"))
      (node (ref "U1") (pin "5") (pinfunction "PF0/OSC_IN_5") (pintype "bidirectional"))
    )
    (net (code "7") (name "/OSC2") (class "Default")
      (node (ref "C26") (pin "1") (pinfunction "1_1") (pintype "passive"))
      (node (ref "Q3") (pin "2") (pinfunction "2_2") (pintype "passive"))
      (node (ref "U1") (pin "6") (pinfunction "PF1/OSC_OUT_6") (pintype "bidirectional"))
    )
    (net (code "8") (name "/PRI_SOURCE") (class "Default")
      (node (ref "C22") (pin "P$2") (pinfunction "2_P$2") (pintype "passive"))
      (node (ref "C25") (pin "2") (pinfunction "2_2") (pintype "passive"))
      (node (ref "H1") (pin "1") (pinfunction "P$1_1") (pintype "bidirectional"))
      (node (ref "H1") (pin "2") (pinfunction "P$1_2") (pintype "bidirectional"))
      (node (ref "H1") (pin "3") (pinfunction "P$2_3") (pintype "bidirectional"))
      (node (ref "H1") (pin "4") (pinfunction "P$2_4") (pintype "bidirectional"))
      (node (ref "Q1") (pin "S") (pinfunction "S_S") (pintype "passive"))
      (node (ref "R118") (pin "2") (pinfunction "2_2") (pintype "passive"))
      (node (ref "R119") (pin "2") (pinfunction "2_2") (pintype "passive"))
      (node (ref "R21") (pin "1") (pinfunction "1_1") (pintype "passive"))
      (node (ref "R30") (pin "1") (pinfunction "1_1") (pintype "passive"))
      (node (ref "R6") (pin "2") (pinfunction "2_2") (pintype "passive"))
    )
    (net (code "9") (name "/REG_INP") (class "Default")
      (node (ref "C47") (pin "1") (pinfunction "1_1") (pintype "passive"))
      (node (ref "D8") (pin "C") (pinfunction "C_C") (pintype "passive"))
      (node (ref "D9") (pin "3") (pinfunction "C_3") (pintype "passive"))
      (node (ref "IC4") (pin "2") (pinfunction "IN_2") (pintype "input"))
      (node (ref "IC4") (pin "4") (pinfunction "IN_4") (pintype "input"))
    )
    (net (code "10") (name "/RES") (class "Default")
      (node (ref "C28") (pin "2") (pinfunction "2_2") (pintype "passive"))
      (node (ref "IC2") (pin "4") (pinfunction "4.LLD_4") (pintype "input"))
      (node (ref "R44") (pin "1") (pinfunction "1_1") (pintype "passive"))
    )
    (net (code "11") (name "/VAUX_DC") (class "Default")
      (node (ref "C110") (pin "2") (pinfunction "2_2") (pintype "passive"))
      (node (ref "C20") (pin "+") (pinfunction "+_+") (pintype "passive"))
      (node (ref "D6") (pin "C") (pinfunction "C_C") (pintype "passive"))
      (node (ref "D7") (pin "C") (pinfunction "C_C") (pintype "passive"))
      (node (ref "R193") (pin "2") (pinfunction "2_2") (pintype "passive"))
      (node (ref "R35") (pin "2") (pinfunction "2_2") (pintype "passive"))
      (node (ref "U2") (pin "5") (pinfunction "VIN_5") (pintype "bidirectional"))
    )
    (net (code "12") (name "/VREF2.1") (class "Default")
      (node (ref "IC3") (pin "1") (pinfunction "VREF_1") (pintype "bidirectional"))
      (node (ref "IC3") (pin "5") (pinfunction "CV+_5") (pintype "input"))
      (node (ref "R61") (pin "2") (pinfunction "2_2") (pintype "passive"))
    )
    (net (code "13") (name "/V_FB2") (class "Default")
      (node (ref "C78") (pin "1") (pinfunction "1_1") (pintype "passive"))
      (node (ref "R134") (pin "1") (pinfunction "1_1") (pintype "passive"))
      (node (ref "R135") (pin "2") (pinfunction "2_2") (pintype "passive"))
      (node (ref "U2") (pin "3") (pinfunction "FB_3") (pintype "bidirectional"))
    )
    (net (code "14") (name "/V_SUPPLY") (class "Default")
      (node (ref "C33") (pin "2") (pinfunction "2_2") (pintype "passive"))
      (node (ref "C34") (pin "2") (pinfunction "2_2") (pintype "passive"))
      (node (ref "C61") (pin "1") (pinfunction "1_1") (pintype "passive"))
      (node (ref "C69") (pin "2") (pinfunction "2_2") (pintype "passive"))
      (node (ref "C79") (pin "2") (pinfunction "2_2") (pintype "passive"))
      (node (ref "C98") (pin "2") (pinfunction "2_2") (pintype "passive"))
      (node (ref "D10") (pin "C") (pinfunction "C_C") (pintype "passive"))
      (node (ref "D8") (pin "A") (pinfunction "A_A") (pintype "passive"))
      (node (ref "IC2") (pin "1") (pinfunction "1.VCC_1") (pintype "power_in"))
      (node (ref "IC9") (pin "8") (pinfunction "V+_8") (pintype "power_in"))
      (node (ref "L5") (pin "1") (pinfunction "2_1") (pintype "passive"))
      (node (ref "OC1") (pin "1") (pinfunction "1_1") (pintype "passive"))
      (node (ref "R107") (pin "2") (pinfunction "2_2") (pintype "passive"))
      (node (ref "R133") (pin "2") (pinfunction "2_2") (pintype "passive"))
      (node (ref "R69") (pin "1") (pinfunction "1_1") (pintype "passive"))
      (node (ref "R88") (pin "2") (pinfunction "2_2") (pintype "passive"))
      (node (ref "R92") (pin "1") (pinfunction "1_1") (pintype "passive"))
      (node (ref "RL1") (pin "1") (pinfunction "1_1") (pintype "passive"))
    )
    (net (code "15") (name "BOOST_INP") (class "Default")
      (node (ref "C63") (pin "1") (pinfunction "1_1") (pintype "passive"))
      (node (ref "R91") (pin "1") (pinfunction "1_1") (pintype "passive"))
      (node (ref "TP1") (pin "TP") (pinfunction "TP_TP") (pintype "input"))
      (node (ref "U1") (pin "15") (pinfunction "PA5_15") (pintype "bidirectional"))
    )
    (net (code "16") (name "CUT_OFF_OUTPUT") (class "Default")
      (node (ref "C71") (pin "1") (pinfunction "1_1") (pintype "passive"))
      (node (ref "D14") (pin "A") (pinfunction "A_A") (pintype "passive"))
      (node (ref "R110") (pin "1") (pinfunction "1_1") (pintype "passive"))
      (node (ref "U1") (pin "16") (pinfunction "PA6_16") (pintype "bidirectional"))
    )
    (net (code "17") (name "EARTH") (class "Default")
      (node (ref "C1") (pin "1") (pinfunction "1_1") (pintype "passive"))
      (node (ref "C11") (pin "1") (pinfunction "1_1") (pintype "passive"))
      (node (ref "C2") (pin "1") (pinfunction "1_1") (pintype "passive"))
      (node (ref "C25") (pin "1") (pinfunction "1_1") (pintype "passive"))
      (node (ref "C27") (pin "1") (pinfunction "1_1") (pintype "passive"))
      (node (ref "C35") (pin "2") (pinfunction "2_2") (pintype "passive"))
      (node (ref "C4") (pin "1") (pinfunction "1_1") (pintype "passive"))
      (node (ref "C5") (pin "2") (pinfunction "2_2") (pintype "passive"))
      (node (ref "C59") (pin "1") (pinfunction "1_1") (pintype "passive"))
      (node (ref "C7") (pin "1") (pinfunction "1_1") (pintype "passive"))
      (node (ref "C73") (pin "2") (pinfunction "2_2") (pintype "passive"))
      (node (ref "C74") (pin "2") (pinfunction "2_2") (pintype "passive"))
      (node (ref "C75") (pin "1") (pinfunction "1_1") (pintype "passive"))
      (node (ref "X1") (pin "3") (pinfunction "1_3") (pintype "passive"))
    )
    (net (code "18") (name "GND") (class "Default")
      (node (ref "B1") (pin "-") (pinfunction "-_-") (pintype "passive"))
      (node (ref "C10") (pin "-") (pinfunction "-_-") (pintype "passive"))
      (node (ref "C12") (pin "-") (pinfunction "-_-") (pintype "passive"))
      (node (ref "C13") (pin "-") (pinfunction "-_-") (pintype "passive"))
      (node (ref "C14") (pin "2") (pinfunction "2_2") (pintype "passive"))
      (node (ref "C15") (pin "2") (pinfunction "2_2") (pintype "passive"))
      (node (ref "C18") (pin "P$2") (pinfunction "2_P$2") (pintype "passive"))
      (node (ref "C29") (pin "1") (pinfunction "1_1") (pintype "passive"))
      (node (ref "C59") (pin "2") (pinfunction "2_2") (pintype "passive"))
      (node (ref "C6") (pin "2") (pinfunction "2_2") (pintype "passive"))
      (node (ref "C7") (pin "2") (pinfunction "2_2") (pintype "passive"))
      (node (ref "C76") (pin "2") (pinfunction "2_2") (pintype "passive"))
      (node (ref "C8") (pin "2") (pinfunction "2_2") (pintype "passive"))
      (node (ref "C82") (pin "2") (pinfunction "2_2") (pintype "passive"))
      (node (ref "C9") (pin "1") (pinfunction "1_1") (pintype "passive"))
      (node (ref "IC1") (pin "4") (pinfunction "GND_4") (pintype "power_in"))
      (node (ref "OC1") (pin "3") (pinfunction "3_3") (pintype "passive"))
      (node (ref "OC2") (pin "3") (pinfunction "3_3") (pintype "passive"))
      (node (ref "R10") (pin "1") (pinfunction "1_1") (pintype "passive"))
      (node (ref "R118") (pin "1") (pinfunction "1_1") (pintype "passive"))
      (node (ref "R119") (pin "1") (pinfunction "1_1") (pintype "passive"))
      (node (ref "R5") (pin "1") (pinfunction "1_1") (pintype "passive"))
      (node (ref "TRF1") (pin "14") (pinfunction "7_14") (pintype "passive"))
      (node (ref "TRF1") (pin "33") (pinfunction "7_33") (pintype "passive"))
      (node (ref "TRF1") (pin "48") (pinfunction "8_48") (pintype "passive"))
      (node (ref "TRF1") (pin "49") (pinfunction "7_49") (pintype "passive"))
      (node (ref "TRF1") (pin "6") (pinfunction "7_6") (pintype "passive"))
      (node (ref "Z1") (pin "1") (pinfunction "A_1") (pintype "passive"))
    )
    (net (code "19") (name "GNDA") (class "Default")
      (node (ref "C110") (pin "1") (pinfunction "1_1") (pintype "passive"))
      (node (ref "C20") (pin "-") (pinfunction "-_-") (pintype "passive"))
      (node (ref "C22") (pin "P$1") (pinfunction "1_P$1") (pintype "passive"))
      (node (ref "C23") (pin "2") (pinfunction "2_2") (pintype "passive"))
      (node (ref "C26") (pin "2") (pinfunction "2_2") (pintype "passive"))
      (node (ref "C28") (pin "1") (pinfunction "1_1") (pintype "passive"))
      (node (ref "C30") (pin "1") (pinfunction "1_1") (pintype "passive"))
      (node (ref "C31") (pin "2") (pinfunction "2_2") (pintype "passive"))
      (node (ref "C32") (pin "2") (pinfunction "2_2") (pintype "passive"))
      (node (ref "C33") (pin "1") (pinfunction "1_1") (pintype "passive"))
      (node (ref "C34") (pin "1") (pinfunction "1_1") (pintype "passive"))
      (node (ref "C35") (pin "1") (pinfunction "1_1") (pintype "passive"))
      (node (ref "C36") (pin "2") (pinfunction "2_2") (pintype "passive"))
      (node (ref "C37") (pin "2") (pinfunction "2_2") (pintype "passive"))
      (node (ref "C38") (pin "2") (pinfunction "2_2") (pintype "passive"))
      (node (ref "C39") (pin "2") (pinfunction "2_2") (pintype "passive"))
      (node (ref "C40") (pin "-") (pinfunction "-_-") (pintype "passive"))
      (node (ref "C40") (pin "-1") (pinfunction "-_-1") (pintype "passive"))
      (node (ref "C41") (pin "2") (pinfunction "2_2") (pintype "passive"))
      (node (ref "C42") (pin "-") (pinfunction "-_-") (pintype "passive"))
      (node (ref "C42") (pin "-1") (pinfunction "-_-1") (pintype "passive"))
      (node (ref "C43") (pin "1") (pinfunction "1_1") (pintype "passive"))
      (node (ref "C44") (pin "2") (pinfunction "2_2") (pintype "passive"))
      (node (ref "C45") (pin "2") (pinfunction "2_2") (pintype "passive"))
      (node (ref "C47") (pin "2") (pinfunction "2_2") (pintype "passive"))
      (node (ref "C48") (pin "2") (pinfunction "2_2") (pintype "passive"))
      (node (ref "C49") (pin "2") (pinfunction "2_2") (pintype "passive"))
      (node (ref "C51") (pin "2") (pinfunction "2_2") (pintype "passive"))
      (node (ref "C53") (pin "2") (pinfunction "2_2") (pintype "passive"))
      (node (ref "C54") (pin "2") (pinfunction "2_2") (pintype "passive"))
      (node (ref "C55") (pin "2") (pinfunction "2_2") (pintype "passive"))
      (node (ref "C57") (pin "2") (pinfunction "2_2") (pintype "passive"))
      (node (ref "C60") (pin "1") (pinfunction "1_1") (pintype "passive"))
      (node (ref "C61") (pin "2") (pinfunction "2_2") (pintype "passive"))
      (node (ref "C62") (pin "1") (pinfunction "1_1") (pintype "passive"))
      (node (ref "C63") (pin "2") (pinfunction "2_2") (pintype "passive"))
      (node (ref "C64") (pin "2") (pinfunction "2_2") (pintype "passive"))
      (node (ref "C65") (pin "1") (pinfunction "1_1") (pintype "passive"))
      (node (ref "C66") (pin "2") (pinfunction "2_2") (pintype "passive"))
      (node (ref "C67") (pin "2") (pinfunction "2_2") (pintype "passive"))
      (node (ref "C68") (pin "1") (pinfunction "1_1") (pintype "passive"))
      (node (ref "C69") (pin "1") (pinfunction "1_1") (pintype "passive"))
      (node (ref "C70") (pin "1") (pinfunction "1_1") (pintype "passive"))
      (node (ref "C72") (pin "1") (pinfunction "1_1") (pintype "passive"))
      (node (ref "C75") (pin "2") (pinfunction "2_2") (pintype "passive"))
      (node (ref "C78") (pin "2") (pinfunction "2_2") (pintype "passive"))
      (node (ref "C79") (pin "1") (pinfunction "1_1") (pintype "passive"))
      (node (ref "C98") (pin "1") (pinfunction "1_1") (pintype "passive"))
      (node (ref "D12") (pin "A1") (pinfunction "A1_A1") (pintype "passive"))
      (node (ref "D13") (pin "1") (pinfunction "A_1") (pintype "passive"))
      (node (ref "D18") (pin "A") (pinfunction "A_A") (pintype "passive"))
      (node (ref "H2") (pin "1") (pinfunction "P$1_1") (pintype "bidirectional"))
      (node (ref "H2") (pin "2") (pinfunction "P$1_2") (pintype "bidirectional"))
      (node (ref "H2") (pin "3") (pinfunction "P$2_3") (pintype "bidirectional"))
      (node (ref "H2") (pin "4") (pinfunction "P$2_4") (pintype "bidirectional"))
      (node (ref "IC2") (pin "5") (pinfunction "5.TRIG_5") (pintype "output"))
      (node (ref "IC2") (pin "7") (pinfunction "7.GND_7") (pintype "input"))
      (node (ref "IC4") (pin "1") (pinfunction "GND_1") (pintype "input"))
      (node (ref "IC5") (pin "4") (pinfunction "V-_4") (pintype "power_in"))
      (node (ref "IC6") (pin "A") (pinfunction "1_A") (pintype "passive"))
      (node (ref "IC9") (pin "4") (pinfunction "V-_4") (pintype "power_in"))
      (node (ref "L2") (pin "1") (pinfunction "1.GND_1") (pintype "passive"))
      (node (ref "L2") (pin "4") (pinfunction "4.GND_4") (pintype "passive"))
      (node (ref "PROG1") (pin "3") (pinfunction "GND_3") (pintype "passive"))
      (node (ref "PROG2") (pin "3") (pinfunction "GND_3") (pintype "passive"))
      (node (ref "Q2") (pin "S") (pinfunction "S_S") (pintype "passive"))
      (node (ref "R102") (pin "1") (pinfunction "1_1") (pintype "passive"))
      (node (ref "R135") (pin "1") (pinfunction "1_1") (pintype "passive"))
      (node (ref "R38") (pin "2") (pinfunction "2_2") (pintype "passive"))
      (node (ref "R39") (pin "2") (pinfunction "2_2") (pintype "passive"))
      (node (ref "R40") (pin "2") (pinfunction "2_2") (pintype "passive"))
      (node (ref "R41") (pin "2") (pinfunction "2_2") (pintype "passive"))
      (node (ref "R42") (pin "2") (pinfunction "2_2") (pintype "passive"))
      (node (ref "R43") (pin "2") (pinfunction "2_2") (pintype "passive"))
      (node (ref "R44") (pin "2") (pinfunction "2_2") (pintype "passive"))
      (node (ref "R47") (pin "2") (pinfunction "2_2") (pintype "passive"))
      (node (ref "R48") (pin "2") (pinfunction "2_2") (pintype "passive"))
      (node (ref "R51") (pin "2") (pinfunction "2_2") (pintype "passive"))
      (node (ref "R56") (pin "1") (pinfunction "1_1") (pintype "passive"))
      (node (ref "R58") (pin "2") (pinfunction "2_2") (pintype "passive"))
      (node (ref "R64") (pin "1") (pinfunction "1_1") (pintype "passive"))
      (node (ref "R65") (pin "1") (pinfunction "1_1") (pintype "passive"))
      (node (ref "R68") (pin "1") (pinfunction "1_1") (pintype "passive"))
      (node (ref "R73") (pin "2") (pinfunction "2_2") (pintype "passive"))
      (node (ref "R75") (pin "1") (pinfunction "1_1") (pintype "passive"))
      (node (ref "R81") (pin "2") (pinfunction "2_2") (pintype "passive"))
      (node (ref "R82") (pin "2") (pinfunction "2_2") (pintype "passive"))
      (node (ref "R87") (pin "1") (pinfunction "1_1") (pintype "passive"))
      (node (ref "R90") (pin "1") (pinfunction "1_1") (pintype "passive"))
      (node (ref "R99") (pin "1") (pinfunction "1_1") (pintype "passive"))
      (node (ref "T5") (pin "2") (pinfunction "E_2") (pintype "passive"))
      (node (ref "T6") (pin "2") (pinfunction "E_2") (pintype "passive"))
      (node (ref "TRF1") (pin "24") (pinfunction "10_24") (pintype "passive"))
      (node (ref "TRF1") (pin "27") (pinfunction "10_27") (pintype "passive"))
      (node (ref "TRF1") (pin "40") (pinfunction "9_40") (pintype "passive"))
      (node (ref "TRF1") (pin "41") (pinfunction "10_41") (pintype "passive"))
      (node (ref "TRF1") (pin "6.1") (pinfunction "9_6.1") (pintype "passive"))
      (node (ref "TRF1") (pin "6.2") (pinfunction "9_6.2") (pintype "passive"))
      (node (ref "TRF1") (pin "6.5") (pinfunction "9_6.5") (pintype "passive"))
      (node (ref "TRF1") (pin "7") (pinfunction "10_7") (pintype "passive"))
      (node (ref "TVS1") (pin "A") (pinfunction "1_A") (pintype "passive"))
      (node (ref "U1") (pin "23") (pinfunction "VSS.._23") (pintype "bidirectional"))
      (node (ref "U1") (pin "35") (pinfunction "VSS_35") (pintype "bidirectional"))
      (node (ref "U1") (pin "47") (pinfunction "VSS._47") (pintype "bidirectional"))
      (node (ref "U1") (pin "8") (pinfunction "VSSA_8") (pintype "bidirectional"))
      (node (ref "U2") (pin "2") (pinfunction "GND_2") (pintype "bidirectional"))
      (node (ref "X2") (pin "GND") (pinfunction "GND_GND") (pintype "bidirectional"))
      (node (ref "X2") (pin "SHLD1") (pinfunction "1_SHLD1") (pintype "bidirectional"))
      (node (ref "X2") (pin "SHLD2") (pinfunction "2_SHLD2") (pintype "bidirectional"))
      (node (ref "X4") (pin "1") (pinfunction "1_1") (pintype "passive"))
      (node (ref "Z4") (pin "1") (pinfunction "A_1") (pintype "passive"))
      (node (ref "Z6") (pin "1") (pinfunction "A_1") (pintype "passive"))
    )
    (net (code "20") (name "GNDIO") (class "Default")
      (node (ref "D15") (pin "C") (pinfunction "C_C") (pintype "passive"))
      (node (ref "IC8") (pin "D") (pinfunction "D5678_D") (pintype "passive"))
      (node (ref "IC8") (pin "D1") (pinfunction "D5678_D1") (pintype "passive"))
      (node (ref "IC8") (pin "D2") (pinfunction "D5678_D2") (pintype "passive"))
      (node (ref "IC8") (pin "D3") (pinfunction "D5678_D3") (pintype "passive"))
      (node (ref "IC8") (pin "P$1") (pinfunction "D5678_P$1") (pintype "passive"))
      (node (ref "IC8") (pin "P$2") (pinfunction "D5678_P$2") (pintype "passive"))
      (node (ref "IC8") (pin "P$3") (pinfunction "D5678_P$3") (pintype "passive"))
      (node (ref "R57") (pin "1") (pinfunction "1_1") (pintype "passive"))
      (node (ref "T10") (pin "E") (pinfunction "E_E") (pintype "passive"))
      (node (ref "X3") (pin "2") (pinfunction "1_2") (pintype "passive"))
    )
    (net (code "21") (name "I_OUT_ADC") (class "Default")
      (node (ref "C62") (pin "2") (pinfunction "2_2") (pintype "passive"))
      (node (ref "R83") (pin "2") (pinfunction "2_2") (pintype "passive"))
      (node (ref "U1") (pin "17") (pinfunction "PA7_17") (pintype "bidirectional"))
    )
    (net (code "22") (name "I_PWM") (class "Default")
      (node (ref "R55") (pin "2") (pinfunction "2_2") (pintype "passive"))
      (node (ref "U1") (pin "18") (pinfunction "PB0_18") (pintype "bidirectional"))
    )
    (net (code "23") (name "JTDO") (class "Default")
      (node (ref "PROG1") (pin "6") (pinfunction "PRG_SWO_6") (pintype "passive"))
      (node (ref "PROG2") (pin "6") (pinfunction "PRG_SWO_6") (pintype "passive"))
      (node (ref "U1") (pin "39") (pinfunction "PB3_39") (pintype "bidirectional"))
    )
    (net (code "24") (name "LED_B") (class "Default")
      (node (ref "R52") (pin "1") (pinfunction "1_1") (pintype "passive"))
      (node (ref "U1") (pin "41") (pinfunction "PB5_41") (pintype "bidirectional"))
    )
    (net (code "25") (name "LED_G") (class "Default")
      (node (ref "R53") (pin "1") (pinfunction "1_1") (pintype "passive"))
      (node (ref "U1") (pin "40") (pinfunction "PB4_40") (pintype "bidirectional"))
    )
    (net (code "26") (name "LED_R") (class "Default")
      (node (ref "R49") (pin "1") (pinfunction "1_1") (pintype "passive"))
      (node (ref "U1") (pin "42") (pinfunction "PB6_42") (pintype "bidirectional"))
    )
    (net (code "27") (name "NRST") (class "Default")
      (node (ref "C30") (pin "2") (pinfunction "2_2") (pintype "passive"))
      (node (ref "PROG1") (pin "5") (pinfunction "NRST_5") (pintype "passive"))
      (node (ref "PROG2") (pin "5") (pinfunction "NRST_5") (pintype "passive"))
      (node (ref "R46") (pin "2") (pinfunction "2_2") (pintype "passive"))
      (node (ref "U1") (pin "7") (pinfunction "NRST_7") (pintype "bidirectional"))
    )
    (net (code "28") (name "Net-(B1-PadAC1)") (class "Default")
      (node (ref "B1") (pin "AC1") (pinfunction "AC1_AC1") (pintype "passive"))
      (node (ref "C4") (pin "2") (pinfunction "2_2") (pintype "passive"))
      (node (ref "C83") (pin "2") (pinfunction "2_2") (pintype "passive"))
      (node (ref "C83") (pin "4") (pinfunction "2_4") (pintype "passive"))
      (node (ref "L1") (pin "4") (pinfunction "4_4") (pintype "passive"))
      (node (ref "L1") (pin "7") (pinfunction "4_7") (pintype "passive"))
    )
    (net (code "29") (name "Net-(B1-PadAC2)") (class "Default")
      (node (ref "B1") (pin "AC2") (pinfunction "AC2_AC2") (pintype "passive"))
      (node (ref "C5") (pin "1") (pinfunction "1_1") (pintype "passive"))
      (node (ref "C83") (pin "1") (pinfunction "1_1") (pintype "passive"))
      (node (ref "C83") (pin "3") (pinfunction "1_3") (pintype "passive"))
      (node (ref "L1") (pin "2") (pinfunction "2_2") (pintype "passive"))
      (node (ref "L1") (pin "6") (pinfunction "2_6") (pintype "passive"))
    )
    (net (code "30") (name "Net-(C1-Pad2)") (class "Default")
      (node (ref "C1") (pin "2") (pinfunction "2_2") (pintype "passive"))
      (node (ref "C3") (pin "2") (pinfunction "2_2") (pintype "passive"))
      (node (ref "C3") (pin "4") (pinfunction "2_4") (pintype "passive"))
      (node (ref "C3") (pin "6") (pinfunction "2_6") (pintype "passive"))
      (node (ref "L1") (pin "3") (pinfunction "3_3") (pintype "passive"))
      (node (ref "L1") (pin "8") (pinfunction "3_8") (pintype "passive"))
      (node (ref "NTC1") (pin "P$1") (pinfunction "1_P$1") (pintype "passive"))
      (node (ref "NTC1") (pin "P$4") (pinfunction "1_P$4") (pintype "passive"))
      (node (ref "R1") (pin "1") (pinfunction "1_1") (pintype "passive"))
      (node (ref "R2") (pin "1") (pinfunction "1_1") (pintype "passive"))
    )
    (net (code "31") (name "Net-(C16-Pad1)") (class "Default")
      (node (ref "C16") (pin "1") (pinfunction "1_1") (pintype "passive"))
      (node (ref "D1") (pin "C") (pinfunction "C_C") (pintype "passive"))
      (node (ref "R13") (pin "2") (pinfunction "2_2") (pintype "passive"))
    )
    (net (code "32") (name "Net-(C16-Pad2)") (class "Default")
      (node (ref "C16") (pin "2") (pinfunction "2_2") (pintype "passive"))
      (node (ref "R19") (pin "1") (pinfunction "1_1") (pintype "passive"))
    )
    (net (code "33") (name "Net-(C17-1-Pad3)") (class "Default")
      (node (ref "C17") (pin "1") (pinfunction "1_1") (pintype "passive"))
      (node (ref "C17") (pin "3") (pinfunction "1_3") (pintype "passive"))
      (node (ref "D4") (pin "A") (pinfunction "A_A") (pintype "passive"))
      (node (ref "Q1") (pin "D") (pinfunction "D_D") (pintype "passive"))
      (node (ref "TRF1") (pin "55") (pinfunction "1_55") (pintype "passive"))
      (node (ref "TRF1") (pin "56") (pinfunction "1_56") (pintype "passive"))
      (node (ref "TRF1") (pin "57") (pinfunction "1_57") (pintype "passive"))
      (node (ref "TRF1") (pin "58") (pinfunction "1_58") (pintype "passive"))
    )
    (net (code "34") (name "Net-(C17-2-Pad4)") (class "Default")
      (node (ref "C17") (pin "2") (pinfunction "2_2") (pintype "passive"))
      (node (ref "C17") (pin "4") (pinfunction "2_4") (pintype "passive"))
      (node (ref "R31") (pin "1") (pinfunction "1_1") (pintype "passive"))
    )
    (net (code "35") (name "Net-(C19-Pad1)") (class "Default")
      (node (ref "C19") (pin "1") (pinfunction "1_1") (pintype "passive"))
      (node (ref "R35") (pin "1") (pinfunction "1_1") (pintype "passive"))
    )
    (net (code "36") (name "Net-(C19-Pad2)") (class "Default")
      (node (ref "C19") (pin "2") (pinfunction "2_2") (pintype "passive"))
      (node (ref "D6") (pin "A") (pinfunction "A_A") (pintype "passive"))
      (node (ref "R22") (pin "1") (pinfunction "1_1") (pintype "passive"))
    )
    (net (code "37") (name "Net-(C21-Pad2)") (class "Default")
      (node (ref "C21") (pin "2") (pinfunction "2_2") (pintype "passive"))
      (node (ref "R39") (pin "1") (pinfunction "1_1") (pintype "passive"))
      (node (ref "R40") (pin "1") (pinfunction "1_1") (pintype "passive"))
      (node (ref "R41") (pin "1") (pinfunction "1_1") (pintype "passive"))
      (node (ref "R42") (pin "1") (pinfunction "1_1") (pintype "passive"))
      (node (ref "R43") (pin "1") (pinfunction "1_1") (pintype "passive"))
    )
    (net (code "38") (name "Net-(C24-2)") (class "Default")
      (node (ref "B1") (pin "+") (pinfunction "+_+") (pintype "passive"))
      (node (ref "C11") (pin "2") (pinfunction "2_2") (pintype "passive"))
      (node (ref "C12") (pin "+") (pinfunction "+_+") (pintype "passive"))
      (node (ref "C24") (pin "P$2") (pinfunction "2_P$2") (pintype "passive"))
      (node (ref "C27") (pin "2") (pinfunction "2_2") (pintype "passive"))
      (node (ref "C76") (pin "1") (pinfunction "1_1") (pintype "passive"))
      (node (ref "C82") (pin "1") (pinfunction "1_1") (pintype "passive"))
      (node (ref "D2") (pin "A") (pinfunction "A_A") (pintype "passive"))
      (node (ref "D3") (pin "A") (pinfunction "A_A") (pintype "passive"))
      (node (ref "R11") (pin "2") (pinfunction "2_2") (pintype "passive"))
      (node (ref "R9") (pin "2") (pinfunction "2_2") (pintype "passive"))
      (node (ref "TRF1") (pin "16") (pinfunction "4_16") (pintype "passive"))
      (node (ref "TRF1") (pin "3") (pinfunction "4_3") (pintype "passive"))
      (node (ref "TRF1") (pin "35") (pinfunction "4_35") (pintype "passive"))
      (node (ref "TRF1") (pin "52") (pinfunction "4_52") (pintype "passive"))
    )
    (net (code "39") (name "Net-(C43-Pad2)") (class "Default")
      (node (ref "C43") (pin "2") (pinfunction "2_2") (pintype "passive"))
      (node (ref "R60") (pin "2") (pinfunction "2_2") (pintype "passive"))
      (node (ref "R62") (pin "2") (pinfunction "2_2") (pintype "passive"))
    )
    (net (code "40") (name "Net-(C52-Pad1)") (class "Default")
      (node (ref "C52") (pin "1") (pinfunction "1_1") (pintype "passive"))
      (node (ref "R70") (pin "1") (pinfunction "1_1") (pintype "passive"))
    )
    (net (code "41") (name "Net-(C56-Pad1)") (class "Default")
      (node (ref "C56") (pin "1") (pinfunction "1_1") (pintype "passive"))
      (node (ref "R76") (pin "1") (pinfunction "1_1") (pintype "passive"))
    )
    (net (code "42") (name "Net-(C68-Pad2)") (class "Default")
      (node (ref "C68") (pin "2") (pinfunction "2_2") (pintype "passive"))
      (node (ref "R103") (pin "1") (pinfunction "1_1") (pintype "passive"))
      (node (ref "R104") (pin "2") (pinfunction "2_2") (pintype "passive"))
    )
    (net (code "43") (name "Net-(C77-Pad1)") (class "Default")
      (node (ref "C77") (pin "1") (pinfunction "1_1") (pintype "passive"))
      (node (ref "R194") (pin "2") (pinfunction "2_2") (pintype "passive"))
    )
    (net (code "44") (name "Net-(D1-PadA)") (class "Default")
      (node (ref "D1") (pin "A") (pinfunction "A_A") (pintype "passive"))
      (node (ref "R19") (pin "2") (pinfunction "2_2") (pintype "passive"))
      (node (ref "R20") (pin "2") (pinfunction "2_2") (pintype "passive"))
    )
    (net (code "45") (name "Net-(D2-PadC)") (class "Default")
      (node (ref "D2") (pin "C") (pinfunction "C_C") (pintype "passive"))
      (node (ref "R17") (pin "1") (pinfunction "1_1") (pintype "passive"))
      (node (ref "R18") (pin "1") (pinfunction "1_1") (pintype "passive"))
    )
    (net (code "46") (name "Net-(D3-PadC)") (class "Default")
      (node (ref "D3") (pin "C") (pinfunction "C_C") (pintype "passive"))
      (node (ref "R23") (pin "1") (pinfunction "1_1") (pintype "passive"))
      (node (ref "R24") (pin "1") (pinfunction "1_1") (pintype "passive"))
    )
    (net (code "47") (name "Net-(D4-PadC)") (class "Default")
      (node (ref "D4") (pin "C") (pinfunction "C_C") (pintype "passive"))
      (node (ref "R17") (pin "2") (pinfunction "2_2") (pintype "passive"))
      (node (ref "R18") (pin "2") (pinfunction "2_2") (pintype "passive"))
      (node (ref "R23") (pin "2") (pinfunction "2_2") (pintype "passive"))
      (node (ref "R24") (pin "2") (pinfunction "2_2") (pintype "passive"))
    )
    (net (code "48") (name "Net-(D5-PadA)") (class "Default")
      (node (ref "D5") (pin "A") (pinfunction "A_A") (pintype "passive"))
      (node (ref "Q1") (pin "G") (pinfunction "G_G") (pintype "passive"))
      (node (ref "R14") (pin "1") (pinfunction "1_1") (pintype "passive"))
      (node (ref "R21") (pin "2") (pinfunction "2_2") (pintype "passive"))
    )
    (net (code "49") (name "Net-(D5-PadC)") (class "Default")
      (node (ref "D5") (pin "C") (pinfunction "C_C") (pintype "passive"))
      (node (ref "R14") (pin "2") (pinfunction "2_2") (pintype "passive"))
      (node (ref "R15") (pin "1") (pinfunction "1_1") (pintype "passive"))
    )
    (net (code "50") (name "Net-(D9-A1)") (class "Default")
      (node (ref "C64") (pin "1") (pinfunction "1_1") (pintype "passive"))
      (node (ref "D9") (pin "1") (pinfunction "A1_1") (pintype "passive"))
      (node (ref "D9") (pin "2") (pinfunction "A2_2") (pintype "passive"))
      (node (ref "R85") (pin "1") (pinfunction "1_1") (pintype "passive"))
      (node (ref "TVS1") (pin "C") (pinfunction "2_C") (pintype "passive"))
    )
    (net (code "51") (name "Net-(D11-PadA)") (class "Default")
      (node (ref "D11") (pin "A") (pinfunction "A_A") (pintype "passive"))
      (node (ref "R93") (pin "1") (pinfunction "1_1") (pintype "passive"))
    )
    (net (code "52") (name "Net-(D15-PadA)") (class "Default")
      (node (ref "D15") (pin "A") (pinfunction "A_A") (pintype "passive"))
      (node (ref "R117") (pin "2") (pinfunction "2_2") (pintype "passive"))
      (node (ref "T10") (pin "B") (pinfunction "B_B") (pintype "passive"))
    )
    (net (code "53") (name "Net-(F1-Pad1)") (class "Default")
      (node (ref "F1") (pin "1") (pinfunction "1_1") (pintype "passive"))
      (node (ref "NTC1") (pin "P$2") (pinfunction "2_P$2") (pintype "passive"))
      (node (ref "NTC1") (pin "P$3") (pinfunction "2_P$3") (pintype "passive"))
    )
    (net (code "54") (name "Net-(F1-Pad2)") (class "Default")
      (node (ref "F1") (pin "2") (pinfunction "2_2") (pintype "passive"))
      (node (ref "X1") (pin "1") (pinfunction "1_1") (pintype "passive"))
    )
    (net (code "55") (name "Net-(IC1-CS)") (class "Default")
      (node (ref "C9") (pin "2") (pinfunction "2_2") (pintype "passive"))
      (node (ref "IC1") (pin "3") (pinfunction "CS_3") (pintype "input"))
      (node (ref "R6") (pin "1") (pinfunction "1_1") (pintype "passive"))
    )
    (net (code "56") (name "Net-(IC1-DRV)") (class "Default")
      (node (ref "IC1") (pin "5") (pinfunction "DRV_5") (pintype "output"))
      (node (ref "R15") (pin "2") (pinfunction "2_2") (pintype "passive"))
    )
    (net (code "57") (name "Net-(IC1-FAULT)") (class "Default")
      (node (ref "C6") (pin "1") (pinfunction "1_1") (pintype "passive"))
      (node (ref "IC1") (pin "1") (pinfunction "FAULT_1") (pintype "power_in"))
      (node (ref "R5") (pin "2") (pinfunction "2_2") (pintype "passive"))
      (node (ref "Z2") (pin "1") (pinfunction "A_1") (pintype "passive"))
    )
    (net (code "58") (name "Net-(IC1-FB)") (class "Default")
      (node (ref "C8") (pin "1") (pinfunction "1_1") (pintype "passive"))
      (node (ref "IC1") (pin "2") (pinfunction "FB_2") (pintype "input"))
      (node (ref "OC1") (pin "4") (pinfunction "4_4") (pintype "passive"))
      (node (ref "OC2") (pin "4") (pinfunction "4_4") (pintype "passive"))
    )
    (net (code "59") (name "Net-(IC1-HV)") (class "Default")
      (node (ref "IC1") (pin "8") (pinfunction "HV_8") (pintype "input"))
      (node (ref "R12") (pin "2") (pinfunction "2_2") (pintype "passive"))
    )
    (net (code "60") (name "Net-(IC1-VCC)") (class "Default")
      (node (ref "C14") (pin "1") (pinfunction "1_1") (pintype "passive"))
      (node (ref "C15") (pin "1") (pinfunction "1_1") (pintype "passive"))
      (node (ref "IC1") (pin "6") (pinfunction "VCC_6") (pintype "input"))
      (node (ref "R16") (pin "2") (pinfunction "2_2") (pintype "passive"))
      (node (ref "Z2") (pin "3") (pinfunction "C_3") (pintype "passive"))
    )
    (net (code "61") (name "Net-(IC2-2.MIN_TOFF)") (class "Default")
      (node (ref "IC2") (pin "2") (pinfunction "2.MIN_TOFF_2") (pintype "input"))
      (node (ref "R48") (pin "1") (pinfunction "1_1") (pintype "passive"))
    )
    (net (code "62") (name "Net-(IC2-3.MIN_TON)") (class "Default")
      (node (ref "IC2") (pin "3") (pinfunction "3.MIN_TON_3") (pintype "input"))
      (node (ref "R47") (pin "1") (pinfunction "1_1") (pintype "passive"))
    )
    (net (code "63") (name "Net-(IC2-8.DRV)") (class "Default")
      (node (ref "IC2") (pin "8") (pinfunction "8.DRV_8") (pintype "input"))
      (node (ref "R36") (pin "1") (pinfunction "1_1") (pintype "passive"))
    )
    (net (code "64") (name "Net-(IC3-CC+)") (class "Default")
      (node (ref "C80") (pin "2") (pinfunction "2_2") (pintype "passive"))
      (node (ref "IC3") (pin "3") (pinfunction "CC+_3") (pintype "input"))
      (node (ref "R62") (pin "1") (pinfunction "1_1") (pintype "passive"))
      (node (ref "R63") (pin "2") (pinfunction "2_2") (pintype "passive"))
    )
    (net (code "65") (name "Net-(IC3-CC-)") (class "Default")
      (node (ref "C80") (pin "1") (pinfunction "1_1") (pintype "passive"))
      (node (ref "IC3") (pin "2") (pinfunction "CC-_2") (pintype "input"))
      (node (ref "R66") (pin "1") (pinfunction "1_1") (pintype "passive"))
      (node (ref "R70") (pin "2") (pinfunction "2_2") (pintype "passive"))
    )
    (net (code "66") (name "Net-(IC3-CV-)") (class "Default")
      (node (ref "IC3") (pin "4") (pinfunction "CV-_4") (pintype "input"))
      (node (ref "R76") (pin "2") (pinfunction "2_2") (pintype "passive"))
      (node (ref "R79") (pin "1") (pinfunction "1_1") (pintype "passive"))
      (node (ref "R80") (pin "2") (pinfunction "2_2") (pintype "passive"))
    )
    (net (code "67") (name "Net-(IC3-OUT)") (class "Default")
      (node (ref "C52") (pin "2") (pinfunction "2_2") (pintype "passive"))
      (node (ref "C56") (pin "2") (pinfunction "2_2") (pintype "passive"))
      (node (ref "IC3") (pin "7") (pinfunction "OUT_7") (pintype "output"))
      (node (ref "R74") (pin "1") (pinfunction "1_1") (pintype "passive"))
    )
    (net (code "68") (name "Net-(IC3-VCC)") (class "Default")
      (node (ref "C46") (pin "2") (pinfunction "2_2") (pintype "passive"))
      (node (ref "IC3") (pin "8") (pinfunction "VCC_8") (pintype "power_in"))
      (node (ref "R69") (pin "2") (pinfunction "2_2") (pintype "passive"))
    )
    (net (code "69") (name "Net-(IC5A--IN)") (class "Default")
      (node (ref "C58") (pin "1") (pinfunction "1_1") (pintype "passive"))
      (node (ref "IC5") (pin "2") (pinfunction "-IN_2") (pintype "input"))
      (node (ref "R75") (pin "2") (pinfunction "2_2") (pintype "passive"))
      (node (ref "R77") (pin "1") (pinfunction "1_1") (pintype "passive"))
    )
    (net (code "70") (name "Net-(IC5A-OUT)") (class "Default")
      (node (ref "C58") (pin "2") (pinfunction "2_2") (pintype "passive"))
      (node (ref "IC5") (pin "1") (pinfunction "OUT_1") (pintype "output"))
      (node (ref "R77") (pin "2") (pinfunction "2_2") (pintype "passive"))
      (node (ref "R83") (pin "1") (pinfunction "1_1") (pintype "passive"))
    )
    (net (code "71") (name "Net-(IC5B-+IN)") (class "Default")
      (node (ref "C81") (pin "2") (pinfunction "2_2") (pintype "passive"))
      (node (ref "IC5") (pin "5") (pinfunction "+IN_5") (pintype "input"))
      (node (ref "R67") (pin "1") (pinfunction "1_1") (pintype "passive"))
    )
    (net (code "72") (name "Net-(IC5B--IN)") (class "Default")
      (node (ref "C50") (pin "1") (pinfunction "1_1") (pintype "passive"))
      (node (ref "C81") (pin "1") (pinfunction "1_1") (pintype "passive"))
      (node (ref "IC5") (pin "6") (pinfunction "-IN_6") (pintype "input"))
      (node (ref "R68") (pin "2") (pinfunction "2_2") (pintype "passive"))
      (node (ref "R71") (pin "1") (pinfunction "1_1") (pintype "passive"))
    )
    (net (code "73") (name "Net-(IC6-2)") (class "Default")
      (node (ref "IC6") (pin "R") (pinfunction "2_R") (pintype "passive"))
      (node (ref "R89") (pin "1") (pinfunction "1_1") (pintype "passive"))
      (node (ref "R90") (pin "2") (pinfunction "2_2") (pintype "passive"))
    )
    (net (code "74") (name "Net-(IC6-3)") (class "Default")
      (node (ref "C65") (pin "2") (pinfunction "2_2") (pintype "passive"))
      (node (ref "IC6") (pin "C") (pinfunction "3_C") (pintype "passive"))
      (node (ref "IC9") (pin "3") (pinfunction "+IN_3") (pintype "input"))
      (node (ref "R88") (pin "1") (pinfunction "1_1") (pintype "passive"))
      (node (ref "R89") (pin "2") (pinfunction "2_2") (pintype "passive"))
    )
    (net (code "75") (name "Net-(IC8-G4)") (class "Default")
      (node (ref "IC8") (pin "GATE") (pinfunction "G4_GATE") (pintype "passive"))
      (node (ref "R107") (pin "1") (pinfunction "1_1") (pintype "passive"))
      (node (ref "R116") (pin "2") (pinfunction "2_2") (pintype "passive"))
      (node (ref "T7") (pin "3") (pinfunction "C_3") (pintype "passive"))
      (node (ref "T9") (pin "3") (pinfunction "C_3") (pintype "passive"))
      (node (ref "Z8") (pin "3") (pinfunction "C_3") (pintype "passive"))
    )
    (net (code "76") (name "Net-(IC9A--IN)") (class "Default")
      (node (ref "IC9") (pin "1") (pinfunction "OUT_1") (pintype "output"))
      (node (ref "IC9") (pin "2") (pinfunction "-IN_2") (pintype "input"))
      (node (ref "R101") (pin "2") (pinfunction "2_2") (pintype "passive"))
      (node (ref "R98") (pin "2") (pinfunction "2_2") (pintype "passive"))
    )
    (net (code "77") (name "Net-(IC9B-+IN)") (class "Default")
      (node (ref "D12") (pin "A") (pinfunction "A_A") (pintype "passive"))
      (node (ref "IC9") (pin "5") (pinfunction "+IN_5") (pintype "input"))
      (node (ref "R105") (pin "1") (pinfunction "1_1") (pintype "passive"))
      (node (ref "R94") (pin "2") (pinfunction "2_2") (pintype "passive"))
      (node (ref "R98") (pin "1") (pinfunction "1_1") (pintype "passive"))
    )
    (net (code "78") (name "Net-(IC9B--IN)") (class "Default")
      (node (ref "IC9") (pin "6") (pinfunction "-IN_6") (pintype "input"))
      (node (ref "R101") (pin "1") (pinfunction "1_1") (pintype "passive"))
      (node (ref "R102") (pin "2") (pinfunction "2_2") (pintype "passive"))
      (node (ref "R106") (pin "1") (pinfunction "1_1") (pintype "passive"))
    )
    (net (code "79") (name "Net-(IC9B-OUT)") (class "Default")
      (node (ref "IC9") (pin "7") (pinfunction "OUT_7") (pintype "output"))
      (node (ref "R105") (pin "2") (pinfunction "2_2") (pintype "passive"))
      (node (ref "R106") (pin "2") (pinfunction "2_2") (pintype "passive"))
      (node (ref "R108") (pin "1") (pinfunction "1_1") (pintype "passive"))
    )
    (net (code "80") (name "Net-(L2-Pad2)") (class "Default")
      (node (ref "L2") (pin "2") (pinfunction "2_2") (pintype "passive"))
      (node (ref "X2") (pin "D+") (pinfunction "D+_D+") (pintype "bidirectional"))
    )
    (net (code "81") (name "Net-(L2-Pad3)") (class "Default")
      (node (ref "L2") (pin "3") (pinfunction "3_3") (pintype "passive"))
      (node (ref "X2") (pin "D-") (pinfunction "D-_D-") (pintype "bidirectional"))
    )
    (net (code "82") (name "Net-(L2-Pad5)") (class "Default")
      (node (ref "L2") (pin "5") (pinfunction "5_5") (pintype "passive"))
      (node (ref "R97") (pin "1") (pinfunction "1_1") (pintype "passive"))
    )
    (net (code "83") (name "Net-(L2-Pad6)") (class "Default")
      (node (ref "L2") (pin "6") (pinfunction "6_6") (pintype "passive"))
      (node (ref "R96") (pin "1") (pinfunction "1_1") (pintype "passive"))
    )
    (net (code "84") (name "Net-(L5-1)") (class "Default")
      (node (ref "C77") (pin "2") (pinfunction "2_2") (pintype "passive"))
      (node (ref "D18") (pin "C") (pinfunction "C_C") (pintype "passive"))
      (node (ref "L5") (pin "2") (pinfunction "1_2") (pintype "passive"))
      (node (ref "U2") (pin "6") (pinfunction "LX_6") (pintype "bidirectional"))
    )
    (net (code "85") (name "Net-(LED1-Pad1)") (class "Default")
      (node (ref "LED1") (pin "1") (pinfunction "1_1") (pintype "passive"))
      (node (ref "R49") (pin "2") (pinfunction "2_2") (pintype "passive"))
    )
    (net (code "86") (name "Net-(LED1-Pad3)") (class "Default")
      (node (ref "LED1") (pin "3") (pinfunction "3_3") (pintype "passive"))
      (node (ref "R53") (pin "2") (pinfunction "2_2") (pintype "passive"))
    )
    (net (code "87") (name "Net-(LED1-Pad4)") (class "Default")
      (node (ref "LED1") (pin "4") (pinfunction "4_4") (pintype "passive"))
      (node (ref "R52") (pin "2") (pinfunction "2_2") (pintype "passive"))
    )
    (net (code "88") (name "Net-(OC1-Pad2)") (class "Default")
      (node (ref "OC1") (pin "2") (pinfunction "2_2") (pintype "passive"))
      (node (ref "R74") (pin "2") (pinfunction "2_2") (pintype "passive"))
    )
    (net (code "89") (name "Net-(Q2-PadG)") (class "Default")
      (node (ref "Q2") (pin "G") (pinfunction "G_G") (pintype "passive"))
      (node (ref "R36") (pin "2") (pinfunction "2_2") (pintype "passive"))
      (node (ref "R38") (pin "1") (pinfunction "1_1") (pintype "passive"))
    )
    (net (code "90") (name "Net-(R2-Pad2)") (class "Default")
      (node (ref "R2") (pin "2") (pinfunction "2_2") (pintype "passive"))
      (node (ref "R3") (pin "2") (pinfunction "2_2") (pintype "passive"))
    )
    (net (code "91") (name "Net-(R3-Pad1)") (class "Default")
      (node (ref "R3") (pin "1") (pinfunction "1_1") (pintype "passive"))
      (node (ref "R4") (pin "1") (pinfunction "1_1") (pintype "passive"))
    )
    (net (code "92") (name "Net-(R7-Pad2)") (class "Default")
      (node (ref "R7") (pin "2") (pinfunction "2_2") (pintype "passive"))
      (node (ref "R8") (pin "1") (pinfunction "1_1") (pintype "passive"))
    )
    (net (code "93") (name "Net-(R10-Pad2)") (class "Default")
      (node (ref "R10") (pin "2") (pinfunction "2_2") (pintype "passive"))
      (node (ref "R9") (pin "1") (pinfunction "1_1") (pintype "passive"))
    )
    (net (code "94") (name "Net-(R11-Pad1)") (class "Default")
      (node (ref "R11") (pin "1") (pinfunction "1_1") (pintype "passive"))
      (node (ref "R12") (pin "1") (pinfunction "1_1") (pintype "passive"))
    )
    (net (code "95") (name "Net-(R20-Pad1)") (class "Default")
      (node (ref "R20") (pin "1") (pinfunction "1_1") (pintype "passive"))
      (node (ref "TRF1") (pin "15") (pinfunction "6_15") (pintype "passive"))
      (node (ref "TRF1") (pin "34") (pinfunction "6_34") (pintype "passive"))
      (node (ref "TRF1") (pin "5") (pinfunction "6_5") (pintype "passive"))
      (node (ref "TRF1") (pin "50") (pinfunction "6_50") (pintype "passive"))
    )
    (net (code "96") (name "Net-(R22-Pad2)") (class "Default")
      (node (ref "R22") (pin "2") (pinfunction "2_2") (pintype "passive"))
      (node (ref "TRF1") (pin "23") (pinfunction "11_23") (pintype "passive"))
      (node (ref "TRF1") (pin "28") (pinfunction "11_28") (pintype "passive"))
      (node (ref "TRF1") (pin "42") (pinfunction "11_42") (pintype "passive"))
      (node (ref "TRF1") (pin "8") (pinfunction "11_8") (pintype "passive"))
    )
    (net (code "97") (name "Net-(R30-Pad2)") (class "Default")
      (node (ref "R30") (pin "2") (pinfunction "2_2") (pintype "passive"))
      (node (ref "R34") (pin "1") (pinfunction "1_1") (pintype "passive"))
    )
    (net (code "98") (name "Net-(R31-Pad2)") (class "Default")
      (node (ref "R31") (pin "2") (pinfunction "2_2") (pintype "passive"))
      (node (ref "R33") (pin "2") (pinfunction "2_2") (pintype "passive"))
    )
    (net (code "99") (name "Net-(R33-Pad1)") (class "Default")
      (node (ref "R33") (pin "1") (pinfunction "1_1") (pintype "passive"))
      (node (ref "R34") (pin "2") (pinfunction "2_2") (pintype "passive"))
    )
    (net (code "100") (name "Net-(R54-Pad1)") (class "Default")
      (node (ref "R54") (pin "1") (pinfunction "1_1") (pintype "passive"))
      (node (ref "R59") (pin "2") (pinfunction "2_2") (pintype "passive"))
      (node (ref "R61") (pin "1") (pinfunction "1_1") (pintype "passive"))
      (node (ref "T3") (pin "E") (pinfunction "E_E") (pintype "passive"))
    )
    (net (code "101") (name "Net-(R54-Pad2)") (class "Default")
      (node (ref "R54") (pin "2") (pinfunction "2_2") (pintype "passive"))
      (node (ref "R55") (pin "1") (pinfunction "1_1") (pintype "passive"))
      (node (ref "T3") (pin "B") (pinfunction "B_B") (pintype "passive"))
    )
    (net (code "102") (name "Net-(R59-Pad1)") (class "Default")
      (node (ref "R59") (pin "1") (pinfunction "1_1") (pintype "passive"))
      (node (ref "R60") (pin "1") (pinfunction "1_1") (pintype "passive"))
      (node (ref "T3") (pin "C") (pinfunction "C_C") (pintype "passive"))
    )
    (net (code "103") (name "Net-(R63-Pad1)") (class "Default")
      (node (ref "R63") (pin "1") (pinfunction "1_1") (pintype "passive"))
      (node (ref "R64") (pin "2") (pinfunction "2_2") (pintype "passive"))
    )
    (net (code "104") (name "Net-(R85-Pad2)") (class "Default")
      (node (ref "R85") (pin "2") (pinfunction "2_2") (pintype "passive"))
      (node (ref "X2") (pin "VBUS") (pinfunction "VBUS_VBUS") (pintype "bidirectional"))
    )
    (net (code "105") (name "Net-(R112-Pad1)") (class "Default")
      (node (ref "R112") (pin "1") (pinfunction "1_1") (pintype "passive"))
      (node (ref "R115") (pin "1") (pinfunction "1_1") (pintype "passive"))
    )
    (net (code "106") (name "Net-(R115-Pad2)") (class "Default")
      (node (ref "R115") (pin "2") (pinfunction "2_2") (pintype "passive"))
      (node (ref "T10") (pin "C") (pinfunction "C_C") (pintype "passive"))
    )
    (net (code "107") (name "Net-(R133-Pad1)") (class "Default")
      (node (ref "R133") (pin "1") (pinfunction "1_1") (pintype "passive"))
      (node (ref "R134") (pin "2") (pinfunction "2_2") (pintype "passive"))
    )
    (net (code "108") (name "Net-(T1-B)") (class "Default")
      (node (ref "R7") (pin "1") (pinfunction "1_1") (pintype "passive"))
      (node (ref "T1") (pin "1") (pinfunction "B_1") (pintype "passive"))
      (node (ref "Z1") (pin "3") (pinfunction "C_3") (pintype "passive"))
    )
    (net (code "109") (name "Net-(T1-C)") (class "Default")
      (node (ref "C13") (pin "+") (pinfunction "+_+") (pintype "passive"))
      (node (ref "C29") (pin "2") (pinfunction "2_2") (pintype "passive"))
      (node (ref "R13") (pin "1") (pinfunction "1_1") (pintype "passive"))
      (node (ref "R8") (pin "2") (pinfunction "2_2") (pintype "passive"))
      (node (ref "T1") (pin "4") (pinfunction "C_4") (pintype "passive"))
    )
    (net (code "110") (name "Net-(T1-E)") (class "Default")
      (node (ref "C10") (pin "+") (pinfunction "+_+") (pintype "passive"))
      (node (ref "R16") (pin "1") (pinfunction "1_1") (pintype "passive"))
      (node (ref "T1") (pin "3") (pinfunction "E_3") (pintype "passive"))
    )
    (net (code "111") (name "Net-(T4-B)") (class "Default")
      (node (ref "C60") (pin "2") (pinfunction "2_2") (pintype "passive"))
      (node (ref "R82") (pin "1") (pinfunction "1_1") (pintype "passive"))
      (node (ref "R84") (pin "2") (pinfunction "2_2") (pintype "passive"))
      (node (ref "T4") (pin "1") (pinfunction "B_1") (pintype "passive"))
    )
    (net (code "112") (name "Net-(T4-C)") (class "Default")
      (node (ref "R78") (pin "1") (pinfunction "1_1") (pintype "passive"))
      (node (ref "R79") (pin "2") (pinfunction "2_2") (pintype "passive"))
      (node (ref "T4") (pin "3") (pinfunction "C_3") (pintype "passive"))
    )
    (net (code "113") (name "Net-(T4-E)") (class "Default")
      (node (ref "R81") (pin "1") (pinfunction "1_1") (pintype "passive"))
      (node (ref "T4") (pin "2") (pinfunction "E_2") (pintype "passive"))
    )
    (net (code "114") (name "Net-(T5-B)") (class "Default")
      (node (ref "R86") (pin "1") (pinfunction "1_1") (pintype "passive"))
      (node (ref "R87") (pin "2") (pinfunction "2_2") (pintype "passive"))
      (node (ref "T5") (pin "1") (pinfunction "B_1") (pintype "passive"))
    )
    (net (code "115") (name "Net-(T5-C)") (class "Default")
      (node (ref "D10") (pin "A") (pinfunction "A_A") (pintype "passive"))
      (node (ref "RL1") (pin "2") (pinfunction "2_2") (pintype "passive"))
      (node (ref "T5") (pin "3") (pinfunction "C_3") (pintype "passive"))
    )
    (net (code "116") (name "Net-(T6-B)") (class "Default")
      (node (ref "R95") (pin "1") (pinfunction "1_1") (pintype "passive"))
      (node (ref "R99") (pin "2") (pinfunction "2_2") (pintype "passive"))
      (node (ref "T6") (pin "1") (pinfunction "B_1") (pintype "passive"))
    )
    (net (code "117") (name "Net-(T6-C)") (class "Default")
      (node (ref "R104") (pin "1") (pinfunction "1_1") (pintype "passive"))
      (node (ref "T6") (pin "3") (pinfunction "C_3") (pintype "passive"))
      (node (ref "Z6") (pin "3") (pinfunction "C_3") (pintype "passive"))
    )
    (net (code "118") (name "Net-(T7-B)") (class "Default")
      (node (ref "R109") (pin "1") (pinfunction "1_1") (pintype "passive"))
      (node (ref "T7") (pin "1") (pinfunction "B_1") (pintype "passive"))
    )
    (net (code "119") (name "Net-(T9-B)") (class "Default")
      (node (ref "R113") (pin "1") (pinfunction "1_1") (pintype "passive"))
      (node (ref "R114") (pin "1") (pinfunction "1_1") (pintype "passive"))
      (node (ref "T9") (pin "1") (pinfunction "B_1") (pintype "passive"))
    )
    (net (code "120") (name "Net-(TRF1-2-Pad1)") (class "Default")
      (node (ref "TRF1") (pin "1") (pinfunction "2_1") (pintype "passive"))
      (node (ref "TRF1") (pin "17") (pinfunction "3_17") (pintype "passive"))
      (node (ref "TRF1") (pin "18") (pinfunction "2_18") (pintype "passive"))
      (node (ref "TRF1") (pin "2") (pinfunction "3_2") (pintype "passive"))
      (node (ref "TRF1") (pin "36") (pinfunction "3_36") (pintype "passive"))
      (node (ref "TRF1") (pin "37") (pinfunction "2_37") (pintype "passive"))
      (node (ref "TRF1") (pin "53") (pinfunction "3_53") (pintype "passive"))
      (node (ref "TRF1") (pin "54") (pinfunction "2_54") (pintype "passive"))
    )
    (net (code "121") (name "Net-(U1-BOOT0)") (class "Default")
      (node (ref "R56") (pin "2") (pinfunction "2_2") (pintype "passive"))
      (node (ref "U1") (pin "44") (pinfunction "BOOT0_44") (pintype "bidirectional"))
    )
    (net (code "122") (name "Net-(U1-PB15)") (class "Default")
      (node (ref "TP4") (pin "TP") (pinfunction "TP_TP") (pintype "input"))
      (node (ref "U1") (pin "28") (pinfunction "PB15_28") (pintype "bidirectional"))
    )
    (net (code "123") (name "Net-(U1-VDDA)") (class "Default")
      (node (ref "C31") (pin "1") (pinfunction "1_1") (pintype "passive"))
      (node (ref "C32") (pin "1") (pinfunction "1_1") (pintype "passive"))
      (node (ref "R45") (pin "1") (pinfunction "1_1") (pintype "passive"))
      (node (ref "U1") (pin "9") (pinfunction "VDDA_9") (pintype "bidirectional"))
    )
    (net (code "124") (name "Net-(U2-BS)") (class "Default")
      (node (ref "R194") (pin "1") (pinfunction "1_1") (pintype "passive"))
      (node (ref "U2") (pin "1") (pinfunction "BS_1") (pintype "bidirectional"))
    )
    (net (code "125") (name "Net-(U2-EN)") (class "Default")
      (node (ref "R193") (pin "1") (pinfunction "1_1") (pintype "passive"))
      (node (ref "U2") (pin "4") (pinfunction "EN_4") (pintype "bidirectional"))
    )
    (net (code "126") (name "Net-(X1B-1)") (class "Default")
      (node (ref "C2") (pin "2") (pinfunction "2_2") (pintype "passive"))
      (node (ref "C3") (pin "1") (pinfunction "1_1") (pintype "passive"))
      (node (ref "C3") (pin "3") (pinfunction "1_3") (pintype "passive"))
      (node (ref "C3") (pin "5") (pinfunction "1_5") (pintype "passive"))
      (node (ref "L1") (pin "1") (pinfunction "1_1") (pintype "passive"))
      (node (ref "L1") (pin "5") (pinfunction "1_5") (pintype "passive"))
      (node (ref "R1") (pin "2") (pinfunction "2_2") (pintype "passive"))
      (node (ref "R4") (pin "2") (pinfunction "2_2") (pintype "passive"))
      (node (ref "X1") (pin "2") (pinfunction "1_2") (pintype "passive"))
    )
    (net (code "127") (name "Net-(X3C-1)") (class "Default")
      (node (ref "RL1") (pin "P0") (pinfunction "P0_P0") (pintype "passive"))
      (node (ref "RL1") (pin "P1") (pinfunction "P1_P1") (pintype "passive"))
      (node (ref "X3") (pin "3") (pinfunction "1_3") (pintype "passive"))
    )
    (net (code "128") (name "Net-(X3D-1)") (class "Default")
      (node (ref "RL1") (pin "S0") (pinfunction "S0_S0") (pintype "passive"))
      (node (ref "X3") (pin "4") (pinfunction "1_4") (pintype "passive"))
    )
    (net (code "129") (name "Net-(X4B-1)") (class "Default")
      (node (ref "R94") (pin "1") (pinfunction "1_1") (pintype "passive"))
      (node (ref "X4") (pin "2") (pinfunction "1_2") (pintype "passive"))
    )
    (net (code "130") (name "Net-(X4C-1)") (class "Default")
      (node (ref "D11") (pin "C") (pinfunction "C_C") (pintype "passive"))
      (node (ref "X4") (pin "3") (pinfunction "1_3") (pintype "passive"))
    )
    (net (code "131") (name "Net-(Z4-C)") (class "Default")
      (node (ref "R91") (pin "2") (pinfunction "2_2") (pintype "passive"))
      (node (ref "R92") (pin "2") (pinfunction "2_2") (pintype "passive"))
      (node (ref "R93") (pin "2") (pinfunction "2_2") (pintype "passive"))
      (node (ref "Z4") (pin "3") (pinfunction "C_3") (pintype "passive"))
    )
    (net (code "132") (name "Net-(Z5-A)") (class "Default")
      (node (ref "R103") (pin "2") (pinfunction "2_2") (pintype "passive"))
      (node (ref "Z5") (pin "1") (pinfunction "A_1") (pintype "passive"))
    )
    (net (code "133") (name "Net-(Z5-C)") (class "Default")
      (node (ref "OC2") (pin "2") (pinfunction "2_2") (pintype "passive"))
      (node (ref "Z5") (pin "3") (pinfunction "C_3") (pintype "passive"))
    )
    (net (code "134") (name "Net-(Z7-C)") (class "Default")
      (node (ref "D14") (pin "C") (pinfunction "C_C") (pintype "passive"))
      (node (ref "R112") (pin "2") (pinfunction "2_2") (pintype "passive"))
      (node (ref "R113") (pin "2") (pinfunction "2_2") (pintype "passive"))
      (node (ref "Z7") (pin "3") (pinfunction "C_3") (pintype "passive"))
    )
    (net (code "135") (name "OVER_VOLT") (class "Default")
      (node (ref "R95") (pin "2") (pinfunction "2_2") (pintype "passive"))
      (node (ref "U1") (pin "38") (pinfunction "PA15_38") (pintype "bidirectional"))
    )
    (net (code "136") (name "PT100_ADC") (class "Default")
      (node (ref "C70") (pin "2") (pinfunction "2_2") (pintype "passive"))
      (node (ref "D13") (pin "3") (pinfunction "AC_3") (pintype "passive"))
      (node (ref "R108") (pin "2") (pinfunction "2_2") (pintype "passive"))
      (node (ref "U1") (pin "11") (pinfunction "PA1_11") (pintype "bidirectional"))
    )
    (net (code "137") (name "RELAY_OP") (class "Default")
      (node (ref "R86") (pin "2") (pinfunction "2_2") (pintype "passive"))
      (node (ref "U1") (pin "12") (pinfunction "PA2_12") (pintype "bidirectional"))
    )
    (net (code "138") (name "SWCLK") (class "Default")
      (node (ref "PROG1") (pin "2") (pinfunction "PRG_SWCLK_2") (pintype "passive"))
      (node (ref "PROG2") (pin "2") (pinfunction "PRG_SWCLK_2") (pintype "passive"))
      (node (ref "U1") (pin "37") (pinfunction "PA14_37") (pintype "bidirectional"))
    )
    (net (code "139") (name "SWDIO") (class "Default")
      (node (ref "PROG1") (pin "4") (pinfunction "PRG_SWDIO_4") (pintype "passive"))
      (node (ref "PROG2") (pin "4") (pinfunction "PRG_SWDIO_4") (pintype "passive"))
      (node (ref "U1") (pin "34") (pinfunction "PA13_34") (pintype "bidirectional"))
    )
    (net (code "140") (name "USB_DM") (class "Default")
      (node (ref "C66") (pin "1") (pinfunction "1_1") (pintype "passive"))
      (node (ref "R97") (pin "2") (pinfunction "2_2") (pintype "passive"))
      (node (ref "U1") (pin "32") (pinfunction "PA11_32") (pintype "bidirectional"))
    )
    (net (code "141") (name "USB_DP") (class "Default")
      (node (ref "C67") (pin "1") (pinfunction "1_1") (pintype "passive"))
      (node (ref "R100") (pin "1") (pinfunction "1_1") (pintype "passive"))
      (node (ref "R96") (pin "2") (pinfunction "2_2") (pintype "passive"))
      (node (ref "U1") (pin "33") (pinfunction "PA12_33") (pintype "bidirectional"))
    )
    (net (code "142") (name "VBAT_ADC") (class "Default")
      (node (ref "C44") (pin "1") (pinfunction "1_1") (pintype "passive"))
      (node (ref "R57") (pin "2") (pinfunction "2_2") (pintype "passive"))
      (node (ref "R58") (pin "1") (pinfunction "1_1") (pintype "passive"))
      (node (ref "U1") (pin "13") (pinfunction "PA3_13") (pintype "bidirectional"))
    )
    (net (code "143") (name "VOUT+_ADC") (class "Default")
      (node (ref "C41") (pin "1") (pinfunction "1_1") (pintype "passive"))
      (node (ref "R50") (pin "2") (pinfunction "2_2") (pintype "passive"))
      (node (ref "R51") (pin "1") (pinfunction "1_1") (pintype "passive"))
      (node (ref "U1") (pin "14") (pinfunction "PA4_14") (pintype "bidirectional"))
    )
    (net (code "144") (name "V_NTC_ADC") (class "Default")
      (node (ref "C53") (pin "1") (pinfunction "1_1") (pintype "passive"))
      (node (ref "R72") (pin "1") (pinfunction "1_1") (pintype "passive"))
      (node (ref "R73") (pin "1") (pinfunction "1_1") (pintype "passive"))
      (node (ref "U1") (pin "10") (pinfunction "PA0_10") (pintype "bidirectional"))
    )
    (net (code "145") (name "V_PWM") (class "Default")
      (node (ref "R84") (pin "1") (pinfunction "1_1") (pintype "passive"))
      (node (ref "U1") (pin "19") (pinfunction "PB1_19") (pintype "bidirectional"))
    )
    (net (code "146") (name "unconnected-(U1-PA8-Pad29)") (class "Default")
      (node (ref "U1") (pin "29") (pinfunction "PA8_29") (pintype "bidirectional"))
    )
    (net (code "147") (name "unconnected-(U1-PA9-Pad30)") (class "Default")
      (node (ref "U1") (pin "30") (pinfunction "PA9_30") (pintype "bidirectional"))
    )
    (net (code "148") (name "unconnected-(U1-PA10-Pad31)") (class "Default")
      (node (ref "U1") (pin "31") (pinfunction "PA10_31") (pintype "bidirectional"))
    )
    (net (code "149") (name "unconnected-(U1-PB2-Pad20)") (class "Default")
      (node (ref "U1") (pin "20") (pinfunction "PB2_20") (pintype "bidirectional"))
    )
    (net (code "150") (name "unconnected-(U1-PB7-Pad43)") (class "Default")
      (node (ref "U1") (pin "43") (pinfunction "PB7_43") (pintype "bidirectional"))
    )
    (net (code "151") (name "unconnected-(U1-PB8-Pad45)") (class "Default")
      (node (ref "U1") (pin "45") (pinfunction "PB8_45") (pintype "bidirectional"))
    )
    (net (code "152") (name "unconnected-(U1-PB9-Pad46)") (class "Default")
      (node (ref "U1") (pin "46") (pinfunction "PB9_46") (pintype "bidirectional"))
    )
    (net (code "153") (name "unconnected-(U1-PB10-Pad21)") (class "Default")
      (node (ref "U1") (pin "21") (pinfunction "PB10_21") (pintype "bidirectional"))
    )
    (net (code "154") (name "unconnected-(U1-PB11-Pad22)") (class "Default")
      (node (ref "U1") (pin "22") (pinfunction "PB11_22") (pintype "bidirectional"))
    )
    (net (code "155") (name "unconnected-(U1-PB12-Pad25)") (class "Default")
      (node (ref "U1") (pin "25") (pinfunction "PB12_25") (pintype "bidirectional"))
    )
    (net (code "156") (name "unconnected-(U1-PB13-Pad26)") (class "Default")
      (node (ref "U1") (pin "26") (pinfunction "PB13_26") (pintype "bidirectional"))
    )
    (net (code "157") (name "unconnected-(U1-PB14-Pad27)") (class "Default")
      (node (ref "U1") (pin "27") (pinfunction "PB14_27") (pintype "bidirectional"))
    )
    (net (code "158") (name "unconnected-(U1-PC13-Pad2)") (class "Default")
      (node (ref "U1") (pin "2") (pinfunction "PC13_2") (pintype "bidirectional"))
    )
    (net (code "159") (name "unconnected-(U1-PC14{slash}OSC32_IN-Pad3)") (class "Default")
      (node (ref "U1") (pin "3") (pinfunction "PC14/OSC32_IN_3") (pintype "bidirectional"))
    )
    (net (code "160") (name "unconnected-(U1-PC15{slash}OSC32_OUT-Pad4)") (class "Default")
      (node (ref "U1") (pin "4") (pinfunction "PC15/OSC32_OUT_4") (pintype "bidirectional"))
    )
    (net (code "161") (name "unconnected-(U1-VBAT-Pad1)") (class "Default")
      (node (ref "U1") (pin "1") (pinfunction "VBAT_1") (pintype "bidirectional"))
    )
  )
)
